# MMU8Ltqfp.net
KiCad netlist of a schematic drawn in EAGLE
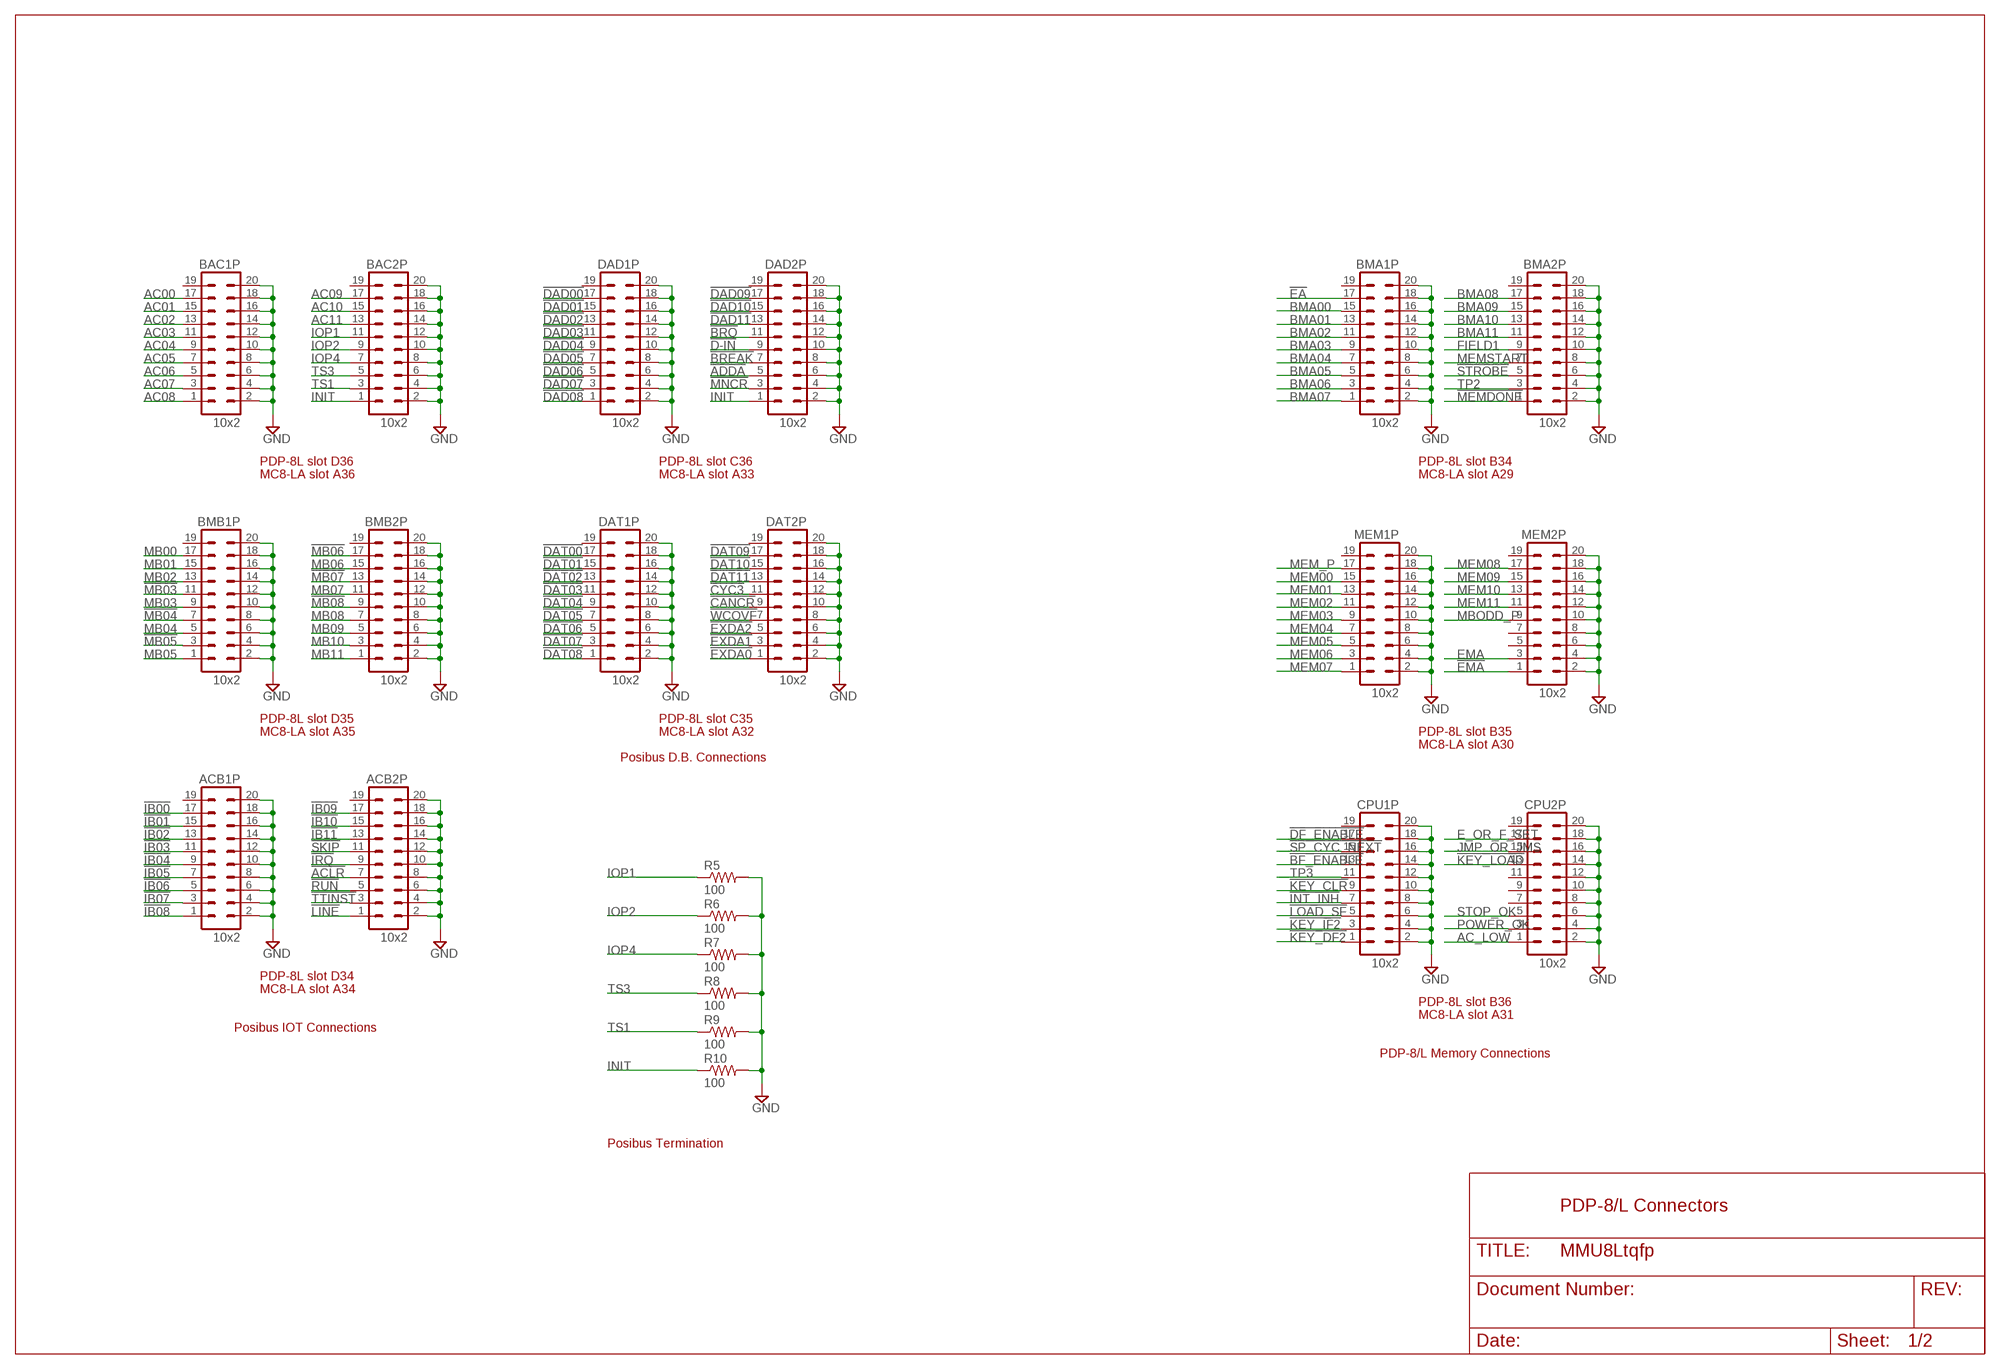
[diagram p0: schematic, sheet 1]
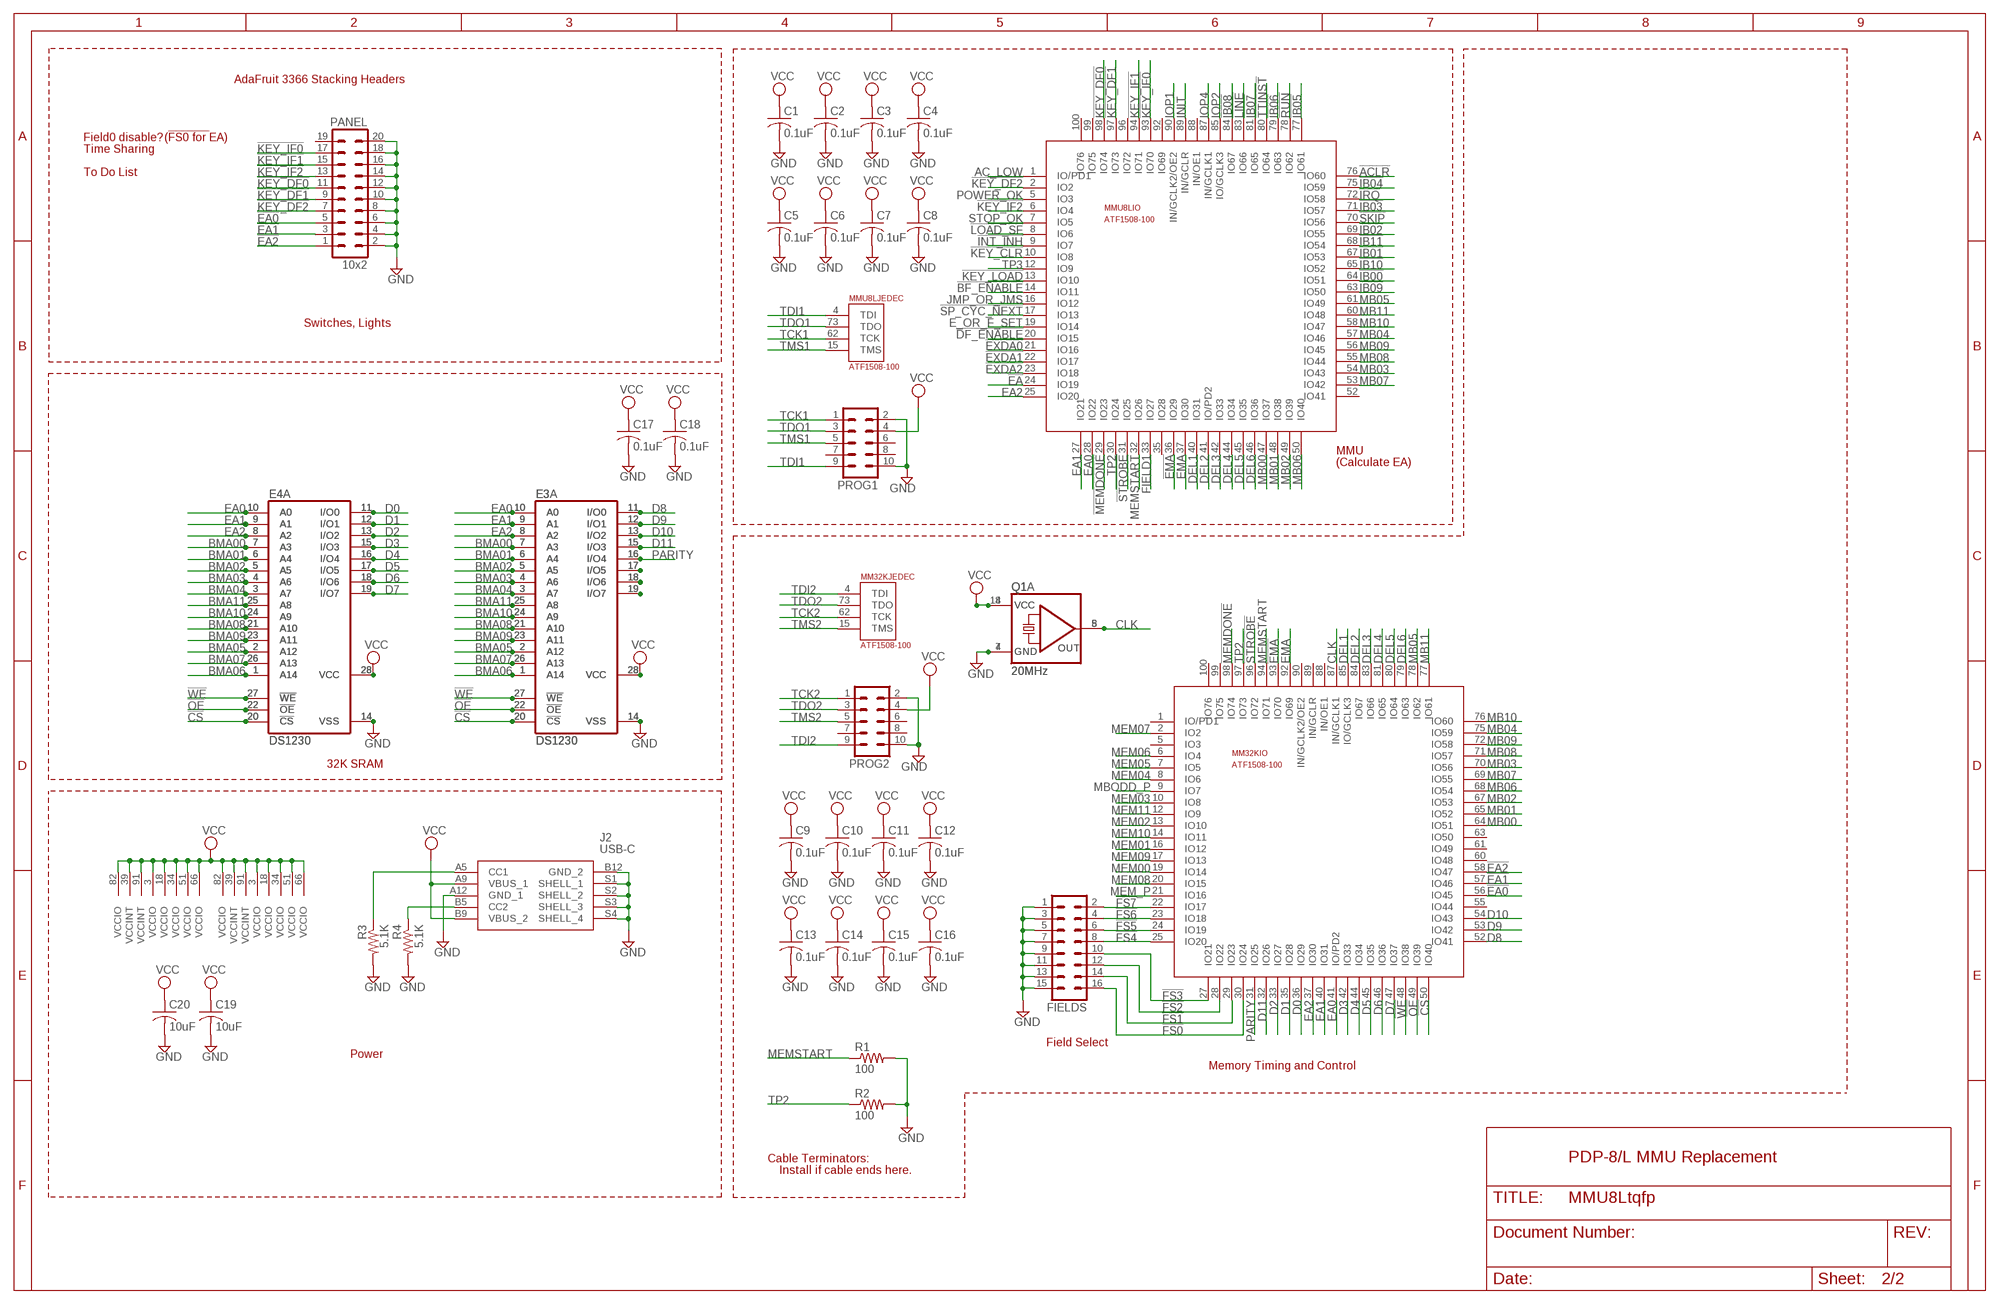
[diagram p1: schematic, sheet 2]

(export (version "E")
  (design (tool "Eeschema 10.0.6"))
  (components
    (comp (ref "ACB1P")
      (value "10x2")
      (footprint "eagle-import:MA10-2")
      (libsource (lib "eagle-import") (part "MA10-2"))
    )
    (comp (ref "ACB2P")
      (value "10x2")
      (footprint "eagle-import:MA10-2")
      (libsource (lib "eagle-import") (part "MA10-2"))
    )
    (comp (ref "BAC1P")
      (value "10x2")
      (footprint "eagle-import:MA10-2")
      (libsource (lib "eagle-import") (part "MA10-2"))
    )
    (comp (ref "BAC2P")
      (value "10x2")
      (footprint "eagle-import:MA10-2")
      (libsource (lib "eagle-import") (part "MA10-2"))
    )
    (comp (ref "BMA1P")
      (value "10x2")
      (footprint "eagle-import:MA10-2")
      (libsource (lib "eagle-import") (part "MA10-2"))
    )
    (comp (ref "BMA2P")
      (value "10x2")
      (footprint "eagle-import:MA10-2")
      (libsource (lib "eagle-import") (part "MA10-2"))
    )
    (comp (ref "BMB1P")
      (value "10x2")
      (footprint "eagle-import:MA10-2")
      (libsource (lib "eagle-import") (part "MA10-2"))
    )
    (comp (ref "BMB2P")
      (value "10x2")
      (footprint "eagle-import:MA10-2")
      (libsource (lib "eagle-import") (part "MA10-2"))
    )
    (comp (ref "CPU1P")
      (value "10x2")
      (footprint "eagle-import:MA10-2")
      (libsource (lib "eagle-import") (part "MA10-2"))
    )
    (comp (ref "CPU2P")
      (value "10x2")
      (footprint "eagle-import:MA10-2")
      (libsource (lib "eagle-import") (part "MA10-2"))
    )
    (comp (ref "DAD1P")
      (value "10x2")
      (footprint "eagle-import:MA10-2")
      (libsource (lib "eagle-import") (part "MA10-2"))
    )
    (comp (ref "DAD2P")
      (value "10x2")
      (footprint "eagle-import:MA10-2")
      (libsource (lib "eagle-import") (part "MA10-2"))
    )
    (comp (ref "DAT1P")
      (value "10x2")
      (footprint "eagle-import:MA10-2")
      (libsource (lib "eagle-import") (part "MA10-2"))
    )
    (comp (ref "DAT2P")
      (value "10x2")
      (footprint "eagle-import:MA10-2")
      (libsource (lib "eagle-import") (part "MA10-2"))
    )
    (comp (ref "MEM1P")
      (value "10x2")
      (footprint "eagle-import:MA10-2")
      (libsource (lib "eagle-import") (part "MA10-2"))
    )
    (comp (ref "MEM2P")
      (value "10x2")
      (footprint "eagle-import:MA10-2")
      (libsource (lib "eagle-import") (part "MA10-2"))
    )
    (comp (ref "R5")
      (value "100")
      (footprint "eagle-import:R1206")
      (libsource (lib "eagle-import") (part "R-US_R1206"))
    )
    (comp (ref "R6")
      (value "100")
      (footprint "eagle-import:R1206")
      (libsource (lib "eagle-import") (part "R-US_R1206"))
    )
    (comp (ref "R7")
      (value "100")
      (footprint "eagle-import:R1206")
      (libsource (lib "eagle-import") (part "R-US_R1206"))
    )
    (comp (ref "R8")
      (value "100")
      (footprint "eagle-import:R1206")
      (libsource (lib "eagle-import") (part "R-US_R1206"))
    )
    (comp (ref "R9")
      (value "100")
      (footprint "eagle-import:R1206")
      (libsource (lib "eagle-import") (part "R-US_R1206"))
    )
    (comp (ref "R10")
      (value "100")
      (footprint "eagle-import:R1206")
      (libsource (lib "eagle-import") (part "R-US_R1206"))
    )
    (comp (ref "C1")
      (value "0.1uF")
      (footprint "eagle-import:C0805")
      (libsource (lib "eagle-import") (part "C-USC0805"))
    )
    (comp (ref "C2")
      (value "0.1uF")
      (footprint "eagle-import:C0805")
      (libsource (lib "eagle-import") (part "C-USC0805"))
    )
    (comp (ref "C3")
      (value "0.1uF")
      (footprint "eagle-import:C0805")
      (libsource (lib "eagle-import") (part "C-USC0805"))
    )
    (comp (ref "C4")
      (value "0.1uF")
      (footprint "eagle-import:C0805")
      (libsource (lib "eagle-import") (part "C-USC0805"))
    )
    (comp (ref "C5")
      (value "0.1uF")
      (footprint "eagle-import:C0805")
      (libsource (lib "eagle-import") (part "C-USC0805"))
    )
    (comp (ref "C6")
      (value "0.1uF")
      (footprint "eagle-import:C0805")
      (libsource (lib "eagle-import") (part "C-USC0805"))
    )
    (comp (ref "C7")
      (value "0.1uF")
      (footprint "eagle-import:C0805")
      (libsource (lib "eagle-import") (part "C-USC0805"))
    )
    (comp (ref "C8")
      (value "0.1uF")
      (footprint "eagle-import:C0805")
      (libsource (lib "eagle-import") (part "C-USC0805"))
    )
    (comp (ref "C9")
      (value "0.1uF")
      (footprint "eagle-import:C0805")
      (libsource (lib "eagle-import") (part "C-USC0805"))
    )
    (comp (ref "C10")
      (value "0.1uF")
      (footprint "eagle-import:C0805")
      (libsource (lib "eagle-import") (part "C-USC0805"))
    )
    (comp (ref "C11")
      (value "0.1uF")
      (footprint "eagle-import:C0805")
      (libsource (lib "eagle-import") (part "C-USC0805"))
    )
    (comp (ref "C12")
      (value "0.1uF")
      (footprint "eagle-import:C0805")
      (libsource (lib "eagle-import") (part "C-USC0805"))
    )
    (comp (ref "C13")
      (value "0.1uF")
      (footprint "eagle-import:C0805")
      (libsource (lib "eagle-import") (part "C-USC0805"))
    )
    (comp (ref "C14")
      (value "0.1uF")
      (footprint "eagle-import:C0805")
      (libsource (lib "eagle-import") (part "C-USC0805"))
    )
    (comp (ref "C15")
      (value "0.1uF")
      (footprint "eagle-import:C0805")
      (libsource (lib "eagle-import") (part "C-USC0805"))
    )
    (comp (ref "C16")
      (value "0.1uF")
      (footprint "eagle-import:C0805")
      (libsource (lib "eagle-import") (part "C-USC0805"))
    )
    (comp (ref "C17")
      (value "0.1uF")
      (footprint "eagle-import:C0805")
      (libsource (lib "eagle-import") (part "C-USC0805"))
    )
    (comp (ref "C18")
      (value "0.1uF")
      (footprint "eagle-import:C0805")
      (libsource (lib "eagle-import") (part "C-USC0805"))
    )
    (comp (ref "C19")
      (value "10uF")
      (footprint "eagle-import:C0805")
      (libsource (lib "eagle-import") (part "C-USC0805"))
    )
    (comp (ref "C20")
      (value "10uF")
      (footprint "eagle-import:C0805")
      (libsource (lib "eagle-import") (part "C-USC0805"))
    )
    (comp (ref "E3")
      (value "DS1230")
      (footprint "eagle-import:DIL28-6")
      (libsource (lib "eagle-import") (part "62256P"))
    )
    (comp (ref "E3A")
      (value "DS1230")
      (footprint "eagle-import:DIL28-3")
      (libsource (lib "eagle-import") (part "62832P"))
    )
    (comp (ref "E4")
      (value "DS1230")
      (footprint "eagle-import:DIL28-6")
      (libsource (lib "eagle-import") (part "62256P"))
    )
    (comp (ref "E4A")
      (value "DS1230")
      (footprint "eagle-import:DIL28-3")
      (libsource (lib "eagle-import") (part "62832P"))
    )
    (comp (ref "FIELDS")
      (value "MA08-2")
      (footprint "eagle-import:MA08-2")
      (libsource (lib "eagle-import") (part "MA08-2"))
    )
    (comp (ref "J2")
      (value "USB-C")
      (footprint "eagle-import:USB497000A")
      (fields (field (name "MANUFACTURER_PART_NUMBER") "USB4970-00-A"))
      (libsource (lib "eagle-import") (part "USB4970-00-A"))
    )
    (comp (ref "MM32K")
      (value "ATF1508-100")
      (footprint "eagle-import:TQFP-100")
      (libsource (lib "eagle-import") (part "ATF150X100TQFP"))
    )
    (comp (ref "MMU8L")
      (value "ATF1508-100")
      (footprint "eagle-import:TQFP-100")
      (libsource (lib "eagle-import") (part "ATF150X100TQFP"))
    )
    (comp (ref "PANEL")
      (value "10x2")
      (footprint "eagle-import:MA10-2")
      (libsource (lib "eagle-import") (part "MA10-2"))
    )
    (comp (ref "PROG1")
      (value "ML10")
      (footprint "eagle-import:ML10")
      (libsource (lib "eagle-import") (part "ML10"))
    )
    (comp (ref "PROG2")
      (value "ML10")
      (footprint "eagle-import:ML10")
      (libsource (lib "eagle-import") (part "ML10"))
    )
    (comp (ref "Q1")
      (value "20MHz")
      (footprint "eagle-import:DIL14S")
      (libsource (lib "eagle-import") (part "QG5860"))
    )
    (comp (ref "Q1A")
      (value "20MHz")
      (footprint "eagle-import:DIL08S")
      (libsource (lib "eagle-import") (part "QG5460"))
    )
    (comp (ref "R1")
      (value "100")
      (footprint "eagle-import:R1206")
      (libsource (lib "eagle-import") (part "R-US_R1206"))
    )
    (comp (ref "R2")
      (value "100")
      (footprint "eagle-import:R1206")
      (libsource (lib "eagle-import") (part "R-US_R1206"))
    )
    (comp (ref "R3")
      (value "5.1K")
      (footprint "eagle-import:R0805")
      (libsource (lib "eagle-import") (part "R-US_R0805"))
    )
    (comp (ref "R4")
      (value "5.1K")
      (footprint "eagle-import:R0805")
      (libsource (lib "eagle-import") (part "R-US_R0805"))
    )
  )
  (nets
    (net (code "1") (name "AC00") (class "Default")
      (node (ref "BAC1P") (pin "17") (pinfunction "17_17") (pintype "passive"))
    )
    (net (code "2") (name "AC01") (class "Default")
      (node (ref "BAC1P") (pin "15") (pinfunction "15_15") (pintype "passive"))
    )
    (net (code "3") (name "AC02") (class "Default")
      (node (ref "BAC1P") (pin "13") (pinfunction "13_13") (pintype "passive"))
    )
    (net (code "4") (name "AC03") (class "Default")
      (node (ref "BAC1P") (pin "11") (pinfunction "11_11") (pintype "passive"))
    )
    (net (code "5") (name "AC04") (class "Default")
      (node (ref "BAC1P") (pin "9") (pinfunction "9_9") (pintype "passive"))
    )
    (net (code "6") (name "AC05") (class "Default")
      (node (ref "BAC1P") (pin "7") (pinfunction "7_7") (pintype "passive"))
    )
    (net (code "7") (name "AC06") (class "Default")
      (node (ref "BAC1P") (pin "5") (pinfunction "5_5") (pintype "passive"))
    )
    (net (code "8") (name "AC07") (class "Default")
      (node (ref "BAC1P") (pin "3") (pinfunction "3_3") (pintype "passive"))
    )
    (net (code "9") (name "AC08") (class "Default")
      (node (ref "BAC1P") (pin "1") (pinfunction "1_1") (pintype "passive"))
    )
    (net (code "10") (name "AC09") (class "Default")
      (node (ref "BAC2P") (pin "17") (pinfunction "17_17") (pintype "passive"))
    )
    (net (code "11") (name "AC10") (class "Default")
      (node (ref "BAC2P") (pin "15") (pinfunction "15_15") (pintype "passive"))
    )
    (net (code "12") (name "AC11") (class "Default")
      (node (ref "BAC2P") (pin "13") (pinfunction "13_13") (pintype "passive"))
    )
    (net (code "13") (name "AC_LOW") (class "Default")
      (node (ref "CPU2P") (pin "1") (pinfunction "1_1") (pintype "passive"))
      (node (ref "MMU8L") (pin "1") (pinfunction "IO/PD1_1") (pintype "bidirectional"))
    )
    (net (code "14") (name "BMA00") (class "Default")
      (node (ref "BMA1P") (pin "15") (pinfunction "15_15") (pintype "passive"))
      (node (ref "E3") (pin "7") (pinfunction "A3_7") (pintype "input"))
      (node (ref "E3A") (pin "7") (pinfunction "A3_7") (pintype "input"))
      (node (ref "E4") (pin "7") (pinfunction "A3_7") (pintype "input"))
      (node (ref "E4A") (pin "7") (pinfunction "A3_7") (pintype "input"))
    )
    (net (code "15") (name "BMA01") (class "Default")
      (node (ref "BMA1P") (pin "13") (pinfunction "13_13") (pintype "passive"))
      (node (ref "E3") (pin "6") (pinfunction "A4_6") (pintype "input"))
      (node (ref "E3A") (pin "6") (pinfunction "A4_6") (pintype "input"))
      (node (ref "E4") (pin "6") (pinfunction "A4_6") (pintype "input"))
      (node (ref "E4A") (pin "6") (pinfunction "A4_6") (pintype "input"))
    )
    (net (code "16") (name "BMA02") (class "Default")
      (node (ref "BMA1P") (pin "11") (pinfunction "11_11") (pintype "passive"))
      (node (ref "E3") (pin "5") (pinfunction "A5_5") (pintype "input"))
      (node (ref "E3A") (pin "5") (pinfunction "A5_5") (pintype "input"))
      (node (ref "E4") (pin "5") (pinfunction "A5_5") (pintype "input"))
      (node (ref "E4A") (pin "5") (pinfunction "A5_5") (pintype "input"))
    )
    (net (code "17") (name "BMA03") (class "Default")
      (node (ref "BMA1P") (pin "9") (pinfunction "9_9") (pintype "passive"))
      (node (ref "E3") (pin "4") (pinfunction "A6_4") (pintype "input"))
      (node (ref "E3A") (pin "4") (pinfunction "A6_4") (pintype "input"))
      (node (ref "E4") (pin "4") (pinfunction "A6_4") (pintype "input"))
      (node (ref "E4A") (pin "4") (pinfunction "A6_4") (pintype "input"))
    )
    (net (code "18") (name "BMA04") (class "Default")
      (node (ref "BMA1P") (pin "7") (pinfunction "7_7") (pintype "passive"))
      (node (ref "E3") (pin "3") (pinfunction "A7_3") (pintype "input"))
      (node (ref "E3A") (pin "3") (pinfunction "A7_3") (pintype "input"))
      (node (ref "E4") (pin "3") (pinfunction "A7_3") (pintype "input"))
      (node (ref "E4A") (pin "3") (pinfunction "A7_3") (pintype "input"))
    )
    (net (code "19") (name "BMA05") (class "Default")
      (node (ref "BMA1P") (pin "5") (pinfunction "5_5") (pintype "passive"))
      (node (ref "E3") (pin "2") (pinfunction "A12_2") (pintype "input"))
      (node (ref "E3A") (pin "2") (pinfunction "A12_2") (pintype "input"))
      (node (ref "E4") (pin "2") (pinfunction "A12_2") (pintype "input"))
      (node (ref "E4A") (pin "2") (pinfunction "A12_2") (pintype "input"))
    )
    (net (code "20") (name "BMA06") (class "Default")
      (node (ref "BMA1P") (pin "3") (pinfunction "3_3") (pintype "passive"))
      (node (ref "E3") (pin "1") (pinfunction "A14_1") (pintype "input"))
      (node (ref "E3A") (pin "1") (pinfunction "A14_1") (pintype "input"))
      (node (ref "E4") (pin "1") (pinfunction "A14_1") (pintype "input"))
      (node (ref "E4A") (pin "1") (pinfunction "A14_1") (pintype "input"))
    )
    (net (code "21") (name "BMA07") (class "Default")
      (node (ref "BMA1P") (pin "1") (pinfunction "1_1") (pintype "passive"))
      (node (ref "E3") (pin "26") (pinfunction "A13_26") (pintype "input"))
      (node (ref "E3A") (pin "26") (pinfunction "A13_26") (pintype "input"))
      (node (ref "E4") (pin "26") (pinfunction "A13_26") (pintype "input"))
      (node (ref "E4A") (pin "26") (pinfunction "A13_26") (pintype "input"))
    )
    (net (code "22") (name "BMA08") (class "Default")
      (node (ref "BMA2P") (pin "17") (pinfunction "17_17") (pintype "passive"))
      (node (ref "E3") (pin "21") (pinfunction "A10_21") (pintype "input"))
      (node (ref "E3A") (pin "21") (pinfunction "A10_21") (pintype "input"))
      (node (ref "E4") (pin "21") (pinfunction "A10_21") (pintype "input"))
      (node (ref "E4A") (pin "21") (pinfunction "A10_21") (pintype "input"))
    )
    (net (code "23") (name "BMA09") (class "Default")
      (node (ref "BMA2P") (pin "15") (pinfunction "15_15") (pintype "passive"))
      (node (ref "E3") (pin "23") (pinfunction "A11_23") (pintype "input"))
      (node (ref "E3A") (pin "23") (pinfunction "A11_23") (pintype "input"))
      (node (ref "E4") (pin "23") (pinfunction "A11_23") (pintype "input"))
      (node (ref "E4A") (pin "23") (pinfunction "A11_23") (pintype "input"))
    )
    (net (code "24") (name "BMA10") (class "Default")
      (node (ref "BMA2P") (pin "13") (pinfunction "13_13") (pintype "passive"))
      (node (ref "E3") (pin "24") (pinfunction "A9_24") (pintype "input"))
      (node (ref "E3A") (pin "24") (pinfunction "A9_24") (pintype "input"))
      (node (ref "E4") (pin "24") (pinfunction "A9_24") (pintype "input"))
      (node (ref "E4A") (pin "24") (pinfunction "A9_24") (pintype "input"))
    )
    (net (code "25") (name "BMA11") (class "Default")
      (node (ref "BMA2P") (pin "11") (pinfunction "11_11") (pintype "passive"))
      (node (ref "E3") (pin "25") (pinfunction "A8_25") (pintype "input"))
      (node (ref "E3A") (pin "25") (pinfunction "A8_25") (pintype "input"))
      (node (ref "E4") (pin "25") (pinfunction "A8_25") (pintype "input"))
      (node (ref "E4A") (pin "25") (pinfunction "A8_25") (pintype "input"))
    )
    (net (code "26") (name "CLK") (class "Default")
      (node (ref "MM32K") (pin "87") (pinfunction "IN/GCLK1_87") (pintype "input"))
      (node (ref "Q1") (pin "8") (pinfunction "OUT_8") (pintype "output"))
      (node (ref "Q1A") (pin "5") (pinfunction "OUT_5") (pintype "output"))
    )
    (net (code "27") (name "D0") (class "Default")
      (node (ref "E4") (pin "11") (pinfunction "I/O0_11") (pintype "bidirectional"))
      (node (ref "E4A") (pin "11") (pinfunction "I/O0_11") (pintype "bidirectional"))
      (node (ref "MM32K") (pin "36") (pinfunction "IO29_36") (pintype "bidirectional"))
    )
    (net (code "28") (name "D1") (class "Default")
      (node (ref "E4") (pin "12") (pinfunction "I/O1_12") (pintype "bidirectional"))
      (node (ref "E4A") (pin "12") (pinfunction "I/O1_12") (pintype "bidirectional"))
      (node (ref "MM32K") (pin "35") (pinfunction "IO28_35") (pintype "bidirectional"))
    )
    (net (code "29") (name "D2") (class "Default")
      (node (ref "E4") (pin "13") (pinfunction "I/O2_13") (pintype "bidirectional"))
      (node (ref "E4A") (pin "13") (pinfunction "I/O2_13") (pintype "bidirectional"))
      (node (ref "MM32K") (pin "33") (pinfunction "IO27_33") (pintype "bidirectional"))
    )
    (net (code "30") (name "D3") (class "Default")
      (node (ref "E4") (pin "15") (pinfunction "I/O3_15") (pintype "bidirectional"))
      (node (ref "E4A") (pin "15") (pinfunction "I/O3_15") (pintype "bidirectional"))
      (node (ref "MM32K") (pin "42") (pinfunction "IO33_42") (pintype "bidirectional"))
    )
    (net (code "31") (name "D4") (class "Default")
      (node (ref "E4") (pin "16") (pinfunction "I/O4_16") (pintype "bidirectional"))
      (node (ref "E4A") (pin "16") (pinfunction "I/O4_16") (pintype "bidirectional"))
      (node (ref "MM32K") (pin "44") (pinfunction "IO34_44") (pintype "bidirectional"))
    )
    (net (code "32") (name "D5") (class "Default")
      (node (ref "E4") (pin "17") (pinfunction "I/O5_17") (pintype "bidirectional"))
      (node (ref "E4A") (pin "17") (pinfunction "I/O5_17") (pintype "bidirectional"))
      (node (ref "MM32K") (pin "45") (pinfunction "IO35_45") (pintype "bidirectional"))
    )
    (net (code "33") (name "D6") (class "Default")
      (node (ref "E4") (pin "18") (pinfunction "I/O6_18") (pintype "bidirectional"))
      (node (ref "E4A") (pin "18") (pinfunction "I/O6_18") (pintype "bidirectional"))
      (node (ref "MM32K") (pin "46") (pinfunction "IO36_46") (pintype "bidirectional"))
    )
    (net (code "34") (name "D7") (class "Default")
      (node (ref "E4") (pin "19") (pinfunction "I/O7_19") (pintype "bidirectional"))
      (node (ref "E4A") (pin "19") (pinfunction "I/O7_19") (pintype "bidirectional"))
      (node (ref "MM32K") (pin "47") (pinfunction "IO37_47") (pintype "bidirectional"))
    )
    (net (code "35") (name "D8") (class "Default")
      (node (ref "E3") (pin "11") (pinfunction "I/O0_11") (pintype "bidirectional"))
      (node (ref "E3A") (pin "11") (pinfunction "I/O0_11") (pintype "bidirectional"))
      (node (ref "MM32K") (pin "52") (pinfunction "IO41_52") (pintype "bidirectional"))
    )
    (net (code "36") (name "D9") (class "Default")
      (node (ref "E3") (pin "12") (pinfunction "I/O1_12") (pintype "bidirectional"))
      (node (ref "E3A") (pin "12") (pinfunction "I/O1_12") (pintype "bidirectional"))
      (node (ref "MM32K") (pin "53") (pinfunction "IO42_53") (pintype "bidirectional"))
    )
    (net (code "37") (name "D10") (class "Default")
      (node (ref "E3") (pin "13") (pinfunction "I/O2_13") (pintype "bidirectional"))
      (node (ref "E3A") (pin "13") (pinfunction "I/O2_13") (pintype "bidirectional"))
      (node (ref "MM32K") (pin "54") (pinfunction "IO43_54") (pintype "bidirectional"))
    )
    (net (code "38") (name "D11") (class "Default")
      (node (ref "E3") (pin "15") (pinfunction "I/O3_15") (pintype "bidirectional"))
      (node (ref "E3A") (pin "15") (pinfunction "I/O3_15") (pintype "bidirectional"))
      (node (ref "MM32K") (pin "32") (pinfunction "IO26_32") (pintype "bidirectional"))
    )
    (net (code "39") (name "DEL1") (class "Default")
      (node (ref "MM32K") (pin "85") (pinfunction "IO/GCLK3_85") (pintype "bidirectional"))
      (node (ref "MMU8L") (pin "40") (pinfunction "IO31_40") (pintype "bidirectional"))
    )
    (net (code "40") (name "DEL2") (class "Default")
      (node (ref "MM32K") (pin "84") (pinfunction "IO67_84") (pintype "bidirectional"))
      (node (ref "MMU8L") (pin "41") (pinfunction "IO/PD2_41") (pintype "bidirectional"))
    )
    (net (code "41") (name "DEL3") (class "Default")
      (node (ref "MM32K") (pin "83") (pinfunction "IO66_83") (pintype "bidirectional"))
      (node (ref "MMU8L") (pin "42") (pinfunction "IO33_42") (pintype "bidirectional"))
    )
    (net (code "42") (name "DEL4") (class "Default")
      (node (ref "MM32K") (pin "81") (pinfunction "IO65_81") (pintype "bidirectional"))
      (node (ref "MMU8L") (pin "44") (pinfunction "IO34_44") (pintype "bidirectional"))
    )
    (net (code "43") (name "DEL5") (class "Default")
      (node (ref "MM32K") (pin "80") (pinfunction "IO64_80") (pintype "bidirectional"))
      (node (ref "MMU8L") (pin "45") (pinfunction "IO35_45") (pintype "bidirectional"))
    )
    (net (code "44") (name "DEL6") (class "Default")
      (node (ref "MM32K") (pin "79") (pinfunction "IO63_79") (pintype "bidirectional"))
      (node (ref "MMU8L") (pin "46") (pinfunction "IO36_46") (pintype "bidirectional"))
    )
    (net (code "45") (name "EA0") (class "Default")
      (node (ref "E3") (pin "10") (pinfunction "A0_10") (pintype "input"))
      (node (ref "E3A") (pin "10") (pinfunction "A0_10") (pintype "input"))
      (node (ref "E4") (pin "10") (pinfunction "A0_10") (pintype "input"))
      (node (ref "E4A") (pin "10") (pinfunction "A0_10") (pintype "input"))
      (node (ref "MM32K") (pin "41") (pinfunction "IO/PD2_41") (pintype "bidirectional"))
      (node (ref "MMU8L") (pin "28") (pinfunction "IO22_28") (pintype "bidirectional"))
    )
    (net (code "46") (name "EA1") (class "Default")
      (node (ref "E3") (pin "9") (pinfunction "A1_9") (pintype "input"))
      (node (ref "E3A") (pin "9") (pinfunction "A1_9") (pintype "input"))
      (node (ref "E4") (pin "9") (pinfunction "A1_9") (pintype "input"))
      (node (ref "E4A") (pin "9") (pinfunction "A1_9") (pintype "input"))
      (node (ref "MM32K") (pin "40") (pinfunction "IO31_40") (pintype "bidirectional"))
      (node (ref "MMU8L") (pin "27") (pinfunction "IO21_27") (pintype "bidirectional"))
    )
    (net (code "47") (name "EA2") (class "Default")
      (node (ref "E3") (pin "8") (pinfunction "A2_8") (pintype "input"))
      (node (ref "E3A") (pin "8") (pinfunction "A2_8") (pintype "input"))
      (node (ref "E4") (pin "8") (pinfunction "A2_8") (pintype "input"))
      (node (ref "E4A") (pin "8") (pinfunction "A2_8") (pintype "input"))
      (node (ref "MM32K") (pin "37") (pinfunction "IO30_37") (pintype "bidirectional"))
      (node (ref "MMU8L") (pin "25") (pinfunction "IO20_25") (pintype "bidirectional"))
    )
    (net (code "48") (name "EMA") (class "Default")
      (node (ref "MEM2P") (pin "3") (pinfunction "3_3") (pintype "passive"))
      (node (ref "MM32K") (pin "92") (pinfunction "IO69_92") (pintype "bidirectional"))
      (node (ref "MMU8L") (pin "37") (pinfunction "IO30_37") (pintype "bidirectional"))
    )
    (net (code "49") (name "E_OR_F_SET") (class "Default")
      (node (ref "CPU2P") (pin "17") (pinfunction "17_17") (pintype "passive"))
      (node (ref "MMU8L") (pin "19") (pinfunction "IO14_19") (pintype "bidirectional"))
    )
    (net (code "50") (name "FIELD1") (class "Default")
      (node (ref "BMA2P") (pin "9") (pinfunction "9_9") (pintype "passive"))
      (node (ref "MMU8L") (pin "33") (pinfunction "IO27_33") (pintype "bidirectional"))
    )
    (net (code "51") (name "GND") (class "Default")
      (node (ref "ACB1P") (pin "10") (pinfunction "10_10") (pintype "passive"))
      (node (ref "ACB1P") (pin "12") (pinfunction "12_12") (pintype "passive"))
      (node (ref "ACB1P") (pin "14") (pinfunction "14_14") (pintype "passive"))
      (node (ref "ACB1P") (pin "16") (pinfunction "16_16") (pintype "passive"))
      (node (ref "ACB1P") (pin "18") (pinfunction "18_18") (pintype "passive"))
      (node (ref "ACB1P") (pin "2") (pinfunction "2_2") (pintype "passive"))
      (node (ref "ACB1P") (pin "20") (pinfunction "20_20") (pintype "passive"))
      (node (ref "ACB1P") (pin "4") (pinfunction "4_4") (pintype "passive"))
      (node (ref "ACB1P") (pin "6") (pinfunction "6_6") (pintype "passive"))
      (node (ref "ACB1P") (pin "8") (pinfunction "8_8") (pintype "passive"))
      (node (ref "ACB2P") (pin "10") (pinfunction "10_10") (pintype "passive"))
      (node (ref "ACB2P") (pin "12") (pinfunction "12_12") (pintype "passive"))
      (node (ref "ACB2P") (pin "14") (pinfunction "14_14") (pintype "passive"))
      (node (ref "ACB2P") (pin "16") (pinfunction "16_16") (pintype "passive"))
      (node (ref "ACB2P") (pin "18") (pinfunction "18_18") (pintype "passive"))
      (node (ref "ACB2P") (pin "2") (pinfunction "2_2") (pintype "passive"))
      (node (ref "ACB2P") (pin "20") (pinfunction "20_20") (pintype "passive"))
      (node (ref "ACB2P") (pin "4") (pinfunction "4_4") (pintype "passive"))
      (node (ref "ACB2P") (pin "6") (pinfunction "6_6") (pintype "passive"))
      (node (ref "ACB2P") (pin "8") (pinfunction "8_8") (pintype "passive"))
      (node (ref "BAC1P") (pin "10") (pinfunction "10_10") (pintype "passive"))
      (node (ref "BAC1P") (pin "12") (pinfunction "12_12") (pintype "passive"))
      (node (ref "BAC1P") (pin "14") (pinfunction "14_14") (pintype "passive"))
      (node (ref "BAC1P") (pin "16") (pinfunction "16_16") (pintype "passive"))
      (node (ref "BAC1P") (pin "18") (pinfunction "18_18") (pintype "passive"))
      (node (ref "BAC1P") (pin "2") (pinfunction "2_2") (pintype "passive"))
      (node (ref "BAC1P") (pin "20") (pinfunction "20_20") (pintype "passive"))
      (node (ref "BAC1P") (pin "4") (pinfunction "4_4") (pintype "passive"))
      (node (ref "BAC1P") (pin "6") (pinfunction "6_6") (pintype "passive"))
      (node (ref "BAC1P") (pin "8") (pinfunction "8_8") (pintype "passive"))
      (node (ref "BAC2P") (pin "10") (pinfunction "10_10") (pintype "passive"))
      (node (ref "BAC2P") (pin "12") (pinfunction "12_12") (pintype "passive"))
      (node (ref "BAC2P") (pin "14") (pinfunction "14_14") (pintype "passive"))
      (node (ref "BAC2P") (pin "16") (pinfunction "16_16") (pintype "passive"))
      (node (ref "BAC2P") (pin "18") (pinfunction "18_18") (pintype "passive"))
      (node (ref "BAC2P") (pin "2") (pinfunction "2_2") (pintype "passive"))
      (node (ref "BAC2P") (pin "20") (pinfunction "20_20") (pintype "passive"))
      (node (ref "BAC2P") (pin "4") (pinfunction "4_4") (pintype "passive"))
      (node (ref "BAC2P") (pin "6") (pinfunction "6_6") (pintype "passive"))
      (node (ref "BAC2P") (pin "8") (pinfunction "8_8") (pintype "passive"))
      (node (ref "BMA1P") (pin "10") (pinfunction "10_10") (pintype "passive"))
      (node (ref "BMA1P") (pin "12") (pinfunction "12_12") (pintype "passive"))
      (node (ref "BMA1P") (pin "14") (pinfunction "14_14") (pintype "passive"))
      (node (ref "BMA1P") (pin "16") (pinfunction "16_16") (pintype "passive"))
      (node (ref "BMA1P") (pin "18") (pinfunction "18_18") (pintype "passive"))
      (node (ref "BMA1P") (pin "2") (pinfunction "2_2") (pintype "passive"))
      (node (ref "BMA1P") (pin "20") (pinfunction "20_20") (pintype "passive"))
      (node (ref "BMA1P") (pin "4") (pinfunction "4_4") (pintype "passive"))
      (node (ref "BMA1P") (pin "6") (pinfunction "6_6") (pintype "passive"))
      (node (ref "BMA1P") (pin "8") (pinfunction "8_8") (pintype "passive"))
      (node (ref "BMA2P") (pin "10") (pinfunction "10_10") (pintype "passive"))
      (node (ref "BMA2P") (pin "12") (pinfunction "12_12") (pintype "passive"))
      (node (ref "BMA2P") (pin "14") (pinfunction "14_14") (pintype "passive"))
      (node (ref "BMA2P") (pin "16") (pinfunction "16_16") (pintype "passive"))
      (node (ref "BMA2P") (pin "18") (pinfunction "18_18") (pintype "passive"))
      (node (ref "BMA2P") (pin "2") (pinfunction "2_2") (pintype "passive"))
      (node (ref "BMA2P") (pin "20") (pinfunction "20_20") (pintype "passive"))
      (node (ref "BMA2P") (pin "4") (pinfunction "4_4") (pintype "passive"))
      (node (ref "BMA2P") (pin "6") (pinfunction "6_6") (pintype "passive"))
      (node (ref "BMA2P") (pin "8") (pinfunction "8_8") (pintype "passive"))
      (node (ref "BMB1P") (pin "10") (pinfunction "10_10") (pintype "passive"))
      (node (ref "BMB1P") (pin "12") (pinfunction "12_12") (pintype "passive"))
      (node (ref "BMB1P") (pin "14") (pinfunction "14_14") (pintype "passive"))
      (node (ref "BMB1P") (pin "16") (pinfunction "16_16") (pintype "passive"))
      (node (ref "BMB1P") (pin "18") (pinfunction "18_18") (pintype "passive"))
      (node (ref "BMB1P") (pin "2") (pinfunction "2_2") (pintype "passive"))
      (node (ref "BMB1P") (pin "20") (pinfunction "20_20") (pintype "passive"))
      (node (ref "BMB1P") (pin "4") (pinfunction "4_4") (pintype "passive"))
      (node (ref "BMB1P") (pin "6") (pinfunction "6_6") (pintype "passive"))
      (node (ref "BMB1P") (pin "8") (pinfunction "8_8") (pintype "passive"))
      (node (ref "BMB2P") (pin "10") (pinfunction "10_10") (pintype "passive"))
      (node (ref "BMB2P") (pin "12") (pinfunction "12_12") (pintype "passive"))
      (node (ref "BMB2P") (pin "14") (pinfunction "14_14") (pintype "passive"))
      (node (ref "BMB2P") (pin "16") (pinfunction "16_16") (pintype "passive"))
      (node (ref "BMB2P") (pin "18") (pinfunction "18_18") (pintype "passive"))
      (node (ref "BMB2P") (pin "2") (pinfunction "2_2") (pintype "passive"))
      (node (ref "BMB2P") (pin "20") (pinfunction "20_20") (pintype "passive"))
      (node (ref "BMB2P") (pin "4") (pinfunction "4_4") (pintype "passive"))
      (node (ref "BMB2P") (pin "6") (pinfunction "6_6") (pintype "passive"))
      (node (ref "BMB2P") (pin "8") (pinfunction "8_8") (pintype "passive"))
      (node (ref "C1") (pin "2") (pinfunction "2_2") (pintype "passive"))
      (node (ref "C10") (pin "2") (pinfunction "2_2") (pintype "passive"))
      (node (ref "C11") (pin "2") (pinfunction "2_2") (pintype "passive"))
      (node (ref "C12") (pin "2") (pinfunction "2_2") (pintype "passive"))
      (node (ref "C13") (pin "2") (pinfunction "2_2") (pintype "passive"))
      (node (ref "C14") (pin "2") (pinfunction "2_2") (pintype "passive"))
      (node (ref "C15") (pin "2") (pinfunction "2_2") (pintype "passive"))
      (node (ref "C16") (pin "2") (pinfunction "2_2") (pintype "passive"))
      (node (ref "C17") (pin "2") (pinfunction "2_2") (pintype "passive"))
      (node (ref "C18") (pin "2") (pinfunction "2_2") (pintype "passive"))
      (node (ref "C19") (pin "2") (pinfunction "2_2") (pintype "passive"))
      (node (ref "C2") (pin "2") (pinfunction "2_2") (pintype "passive"))
      (node (ref "C20") (pin "2") (pinfunction "2_2") (pintype "passive"))
      (node (ref "C3") (pin "2") (pinfunction "2_2") (pintype "passive"))
      (node (ref "C4") (pin "2") (pinfunction "2_2") (pintype "passive"))
      (node (ref "C5") (pin "2") (pinfunction "2_2") (pintype "passive"))
      (node (ref "C6") (pin "2") (pinfunction "2_2") (pintype "passive"))
      (node (ref "C7") (pin "2") (pinfunction "2_2") (pintype "passive"))
      (node (ref "C8") (pin "2") (pinfunction "2_2") (pintype "passive"))
      (node (ref "C9") (pin "2") (pinfunction "2_2") (pintype "passive"))
      (node (ref "CPU1P") (pin "10") (pinfunction "10_10") (pintype "passive"))
      (node (ref "CPU1P") (pin "12") (pinfunction "12_12") (pintype "passive"))
      (node (ref "CPU1P") (pin "14") (pinfunction "14_14") (pintype "passive"))
      (node (ref "CPU1P") (pin "16") (pinfunction "16_16") (pintype "passive"))
      (node (ref "CPU1P") (pin "18") (pinfunction "18_18") (pintype "passive"))
      (node (ref "CPU1P") (pin "2") (pinfunction "2_2") (pintype "passive"))
      (node (ref "CPU1P") (pin "20") (pinfunction "20_20") (pintype "passive"))
      (node (ref "CPU1P") (pin "4") (pinfunction "4_4") (pintype "passive"))
      (node (ref "CPU1P") (pin "6") (pinfunction "6_6") (pintype "passive"))
      (node (ref "CPU1P") (pin "8") (pinfunction "8_8") (pintype "passive"))
      (node (ref "CPU2P") (pin "10") (pinfunction "10_10") (pintype "passive"))
      (node (ref "CPU2P") (pin "12") (pinfunction "12_12") (pintype "passive"))
      (node (ref "CPU2P") (pin "14") (pinfunction "14_14") (pintype "passive"))
      (node (ref "CPU2P") (pin "16") (pinfunction "16_16") (pintype "passive"))
      (node (ref "CPU2P") (pin "18") (pinfunction "18_18") (pintype "passive"))
      (node (ref "CPU2P") (pin "2") (pinfunction "2_2") (pintype "passive"))
      (node (ref "CPU2P") (pin "20") (pinfunction "20_20") (pintype "passive"))
      (node (ref "CPU2P") (pin "4") (pinfunction "4_4") (pintype "passive"))
      (node (ref "CPU2P") (pin "6") (pinfunction "6_6") (pintype "passive"))
      (node (ref "CPU2P") (pin "8") (pinfunction "8_8") (pintype "passive"))
      (node (ref "DAD1P") (pin "10") (pinfunction "10_10") (pintype "passive"))
      (node (ref "DAD1P") (pin "12") (pinfunction "12_12") (pintype "passive"))
      (node (ref "DAD1P") (pin "14") (pinfunction "14_14") (pintype "passive"))
      (node (ref "DAD1P") (pin "16") (pinfunction "16_16") (pintype "passive"))
      (node (ref "DAD1P") (pin "18") (pinfunction "18_18") (pintype "passive"))
      (node (ref "DAD1P") (pin "2") (pinfunction "2_2") (pintype "passive"))
      (node (ref "DAD1P") (pin "20") (pinfunction "20_20") (pintype "passive"))
      (node (ref "DAD1P") (pin "4") (pinfunction "4_4") (pintype "passive"))
      (node (ref "DAD1P") (pin "6") (pinfunction "6_6") (pintype "passive"))
      (node (ref "DAD1P") (pin "8") (pinfunction "8_8") (pintype "passive"))
      (node (ref "DAD2P") (pin "10") (pinfunction "10_10") (pintype "passive"))
      (node (ref "DAD2P") (pin "12") (pinfunction "12_12") (pintype "passive"))
      (node (ref "DAD2P") (pin "14") (pinfunction "14_14") (pintype "passive"))
      (node (ref "DAD2P") (pin "16") (pinfunction "16_16") (pintype "passive"))
      (node (ref "DAD2P") (pin "18") (pinfunction "18_18") (pintype "passive"))
      (node (ref "DAD2P") (pin "2") (pinfunction "2_2") (pintype "passive"))
      (node (ref "DAD2P") (pin "20") (pinfunction "20_20") (pintype "passive"))
      (node (ref "DAD2P") (pin "4") (pinfunction "4_4") (pintype "passive"))
      (node (ref "DAD2P") (pin "6") (pinfunction "6_6") (pintype "passive"))
      (node (ref "DAD2P") (pin "8") (pinfunction "8_8") (pintype "passive"))
      (node (ref "DAT1P") (pin "10") (pinfunction "10_10") (pintype "passive"))
      (node (ref "DAT1P") (pin "12") (pinfunction "12_12") (pintype "passive"))
      (node (ref "DAT1P") (pin "14") (pinfunction "14_14") (pintype "passive"))
      (node (ref "DAT1P") (pin "16") (pinfunction "16_16") (pintype "passive"))
      (node (ref "DAT1P") (pin "18") (pinfunction "18_18") (pintype "passive"))
      (node (ref "DAT1P") (pin "2") (pinfunction "2_2") (pintype "passive"))
      (node (ref "DAT1P") (pin "20") (pinfunction "20_20") (pintype "passive"))
      (node (ref "DAT1P") (pin "4") (pinfunction "4_4") (pintype "passive"))
      (node (ref "DAT1P") (pin "6") (pinfunction "6_6") (pintype "passive"))
      (node (ref "DAT1P") (pin "8") (pinfunction "8_8") (pintype "passive"))
      (node (ref "DAT2P") (pin "10") (pinfunction "10_10") (pintype "passive"))
      (node (ref "DAT2P") (pin "12") (pinfunction "12_12") (pintype "passive"))
      (node (ref "DAT2P") (pin "14") (pinfunction "14_14") (pintype "passive"))
      (node (ref "DAT2P") (pin "16") (pinfunction "16_16") (pintype "passive"))
      (node (ref "DAT2P") (pin "18") (pinfunction "18_18") (pintype "passive"))
      (node (ref "DAT2P") (pin "2") (pinfunction "2_2") (pintype "passive"))
      (node (ref "DAT2P") (pin "20") (pinfunction "20_20") (pintype "passive"))
      (node (ref "DAT2P") (pin "4") (pinfunction "4_4") (pintype "passive"))
      (node (ref "DAT2P") (pin "6") (pinfunction "6_6") (pintype "passive"))
      (node (ref "DAT2P") (pin "8") (pinfunction "8_8") (pintype "passive"))
      (node (ref "E3") (pin "14") (pinfunction "VSS_14") (pintype "power_in"))
      (node (ref "E3A") (pin "14") (pinfunction "VSS_14") (pintype "power_in"))
      (node (ref "E4") (pin "14") (pinfunction "VSS_14") (pintype "power_in"))
      (node (ref "E4A") (pin "14") (pinfunction "VSS_14") (pintype "power_in"))
      (node (ref "FIELDS") (pin "1") (pinfunction "1_1") (pintype "passive"))
      (node (ref "FIELDS") (pin "11") (pinfunction "11_11") (pintype "passive"))
      (node (ref "FIELDS") (pin "13") (pinfunction "13_13") (pintype "passive"))
      (node (ref "FIELDS") (pin "15") (pinfunction "15_15") (pintype "passive"))
      (node (ref "FIELDS") (pin "3") (pinfunction "3_3") (pintype "passive"))
      (node (ref "FIELDS") (pin "5") (pinfunction "5_5") (pintype "passive"))
      (node (ref "FIELDS") (pin "7") (pinfunction "7_7") (pintype "passive"))
      (node (ref "FIELDS") (pin "9") (pinfunction "9_9") (pintype "passive"))
      (node (ref "J2") (pin "A12") (pinfunction "GND_1_A12") (pintype "bidirectional"))
      (node (ref "J2") (pin "B12") (pinfunction "GND_2_B12") (pintype "bidirectional"))
      (node (ref "J2") (pin "S1") (pinfunction "SHELL_1_S1") (pintype "bidirectional"))
      (node (ref "J2") (pin "S2") (pinfunction "SHELL_2_S2") (pintype "bidirectional"))
      (node (ref "J2") (pin "S3") (pinfunction "SHELL_3_S3") (pintype "bidirectional"))
      (node (ref "J2") (pin "S4") (pinfunction "SHELL_4_S4") (pintype "bidirectional"))
      (node (ref "MEM1P") (pin "10") (pinfunction "10_10") (pintype "passive"))
      (node (ref "MEM1P") (pin "12") (pinfunction "12_12") (pintype "passive"))
      (node (ref "MEM1P") (pin "14") (pinfunction "14_14") (pintype "passive"))
      (node (ref "MEM1P") (pin "16") (pinfunction "16_16") (pintype "passive"))
      (node (ref "MEM1P") (pin "18") (pinfunction "18_18") (pintype "passive"))
      (node (ref "MEM1P") (pin "2") (pinfunction "2_2") (pintype "passive"))
      (node (ref "MEM1P") (pin "20") (pinfunction "20_20") (pintype "passive"))
      (node (ref "MEM1P") (pin "4") (pinfunction "4_4") (pintype "passive"))
      (node (ref "MEM1P") (pin "6") (pinfunction "6_6") (pintype "passive"))
      (node (ref "MEM1P") (pin "8") (pinfunction "8_8") (pintype "passive"))
      (node (ref "MEM2P") (pin "10") (pinfunction "10_10") (pintype "passive"))
      (node (ref "MEM2P") (pin "12") (pinfunction "12_12") (pintype "passive"))
      (node (ref "MEM2P") (pin "14") (pinfunction "14_14") (pintype "passive"))
      (node (ref "MEM2P") (pin "16") (pinfunction "16_16") (pintype "passive"))
      (node (ref "MEM2P") (pin "18") (pinfunction "18_18") (pintype "passive"))
      (node (ref "MEM2P") (pin "2") (pinfunction "2_2") (pintype "passive"))
      (node (ref "MEM2P") (pin "20") (pinfunction "20_20") (pintype "passive"))
      (node (ref "MEM2P") (pin "4") (pinfunction "4_4") (pintype "passive"))
      (node (ref "MEM2P") (pin "6") (pinfunction "6_6") (pintype "passive"))
      (node (ref "MEM2P") (pin "8") (pinfunction "8_8") (pintype "passive"))
      (node (ref "PANEL") (pin "10") (pinfunction "10_10") (pintype "passive"))
      (node (ref "PANEL") (pin "12") (pinfunction "12_12") (pintype "passive"))
      (node (ref "PANEL") (pin "14") (pinfunction "14_14") (pintype "passive"))
      (node (ref "PANEL") (pin "16") (pinfunction "16_16") (pintype "passive"))
      (node (ref "PANEL") (pin "18") (pinfunction "18_18") (pintype "passive"))
      (node (ref "PANEL") (pin "2") (pinfunction "2_2") (pintype "passive"))
      (node (ref "PANEL") (pin "20") (pinfunction "20_20") (pintype "passive"))
      (node (ref "PANEL") (pin "4") (pinfunction "4_4") (pintype "passive"))
      (node (ref "PANEL") (pin "6") (pinfunction "6_6") (pintype "passive"))
      (node (ref "PANEL") (pin "8") (pinfunction "8_8") (pintype "passive"))
      (node (ref "PROG1") (pin "10") (pinfunction "10_10") (pintype "passive"))
      (node (ref "PROG1") (pin "2") (pinfunction "2_2") (pintype "passive"))
      (node (ref "PROG2") (pin "10") (pinfunction "10_10") (pintype "passive"))
      (node (ref "PROG2") (pin "2") (pinfunction "2_2") (pintype "passive"))
      (node (ref "Q1") (pin "7") (pinfunction "GND_7") (pintype "power_in"))
      (node (ref "Q1A") (pin "4") (pinfunction "GND_4") (pintype "power_in"))
      (node (ref "R1") (pin "2") (pinfunction "2_2") (pintype "passive"))
      (node (ref "R10") (pin "2") (pinfunction "2_2") (pintype "passive"))
      (node (ref "R2") (pin "2") (pinfunction "2_2") (pintype "passive"))
      (node (ref "R3") (pin "2") (pinfunction "2_2") (pintype "passive"))
      (node (ref "R4") (pin "2") (pinfunction "2_2") (pintype "passive"))
      (node (ref "R5") (pin "2") (pinfunction "2_2") (pintype "passive"))
      (node (ref "R6") (pin "2") (pinfunction "2_2") (pintype "passive"))
      (node (ref "R7") (pin "2") (pinfunction "2_2") (pintype "passive"))
      (node (ref "R8") (pin "2") (pinfunction "2_2") (pintype "passive"))
      (node (ref "R9") (pin "2") (pinfunction "2_2") (pintype "passive"))
    )
    (net (code "52") (name "INIT") (class "Default")
      (node (ref "BAC2P") (pin "1") (pinfunction "1_1") (pintype "passive"))
      (node (ref "DAD2P") (pin "1") (pinfunction "1_1") (pintype "passive"))
      (node (ref "MMU8L") (pin "89") (pinfunction "IN/GCLR_89") (pintype "input"))
      (node (ref "R10") (pin "1") (pinfunction "1_1") (pintype "passive"))
    )
    (net (code "53") (name "IOP1") (class "Default")
      (node (ref "BAC2P") (pin "11") (pinfunction "11_11") (pintype "passive"))
      (node (ref "MMU8L") (pin "90") (pinfunction "IN/GCLK2/OE2_90") (pintype "input"))
      (node (ref "R5") (pin "1") (pinfunction "1_1") (pintype "passive"))
    )
    (net (code "54") (name "IOP2") (class "Default")
      (node (ref "BAC2P") (pin "9") (pinfunction "9_9") (pintype "passive"))
      (node (ref "MMU8L") (pin "85") (pinfunction "IO/GCLK3_85") (pintype "bidirectional"))
      (node (ref "R6") (pin "1") (pinfunction "1_1") (pintype "passive"))
    )
    (net (code "55") (name "IOP4") (class "Default")
      (node (ref "BAC2P") (pin "7") (pinfunction "7_7") (pintype "passive"))
      (node (ref "MMU8L") (pin "87") (pinfunction "IN/GCLK1_87") (pintype "input"))
      (node (ref "R7") (pin "1") (pinfunction "1_1") (pintype "passive"))
    )
    (net (code "56") (name "JMP_OR_JMS") (class "Default")
      (node (ref "CPU2P") (pin "15") (pinfunction "15_15") (pintype "passive"))
      (node (ref "MMU8L") (pin "16") (pinfunction "IO12_16") (pintype "bidirectional"))
    )
    (net (code "57") (name "MB00") (class "Default")
      (node (ref "BMB1P") (pin "17") (pinfunction "17_17") (pintype "passive"))
      (node (ref "MM32K") (pin "64") (pinfunction "IO51_64") (pintype "bidirectional"))
      (node (ref "MMU8L") (pin "47") (pinfunction "IO37_47") (pintype "bidirectional"))
    )
    (net (code "58") (name "MB01") (class "Default")
      (node (ref "BMB1P") (pin "15") (pinfunction "15_15") (pintype "passive"))
      (node (ref "MM32K") (pin "65") (pinfunction "IO52_65") (pintype "bidirectional"))
      (node (ref "MMU8L") (pin "48") (pinfunction "IO38_48") (pintype "bidirectional"))
    )
    (net (code "59") (name "MB02") (class "Default")
      (node (ref "BMB1P") (pin "13") (pinfunction "13_13") (pintype "passive"))
      (node (ref "MM32K") (pin "67") (pinfunction "IO53_67") (pintype "bidirectional"))
      (node (ref "MMU8L") (pin "49") (pinfunction "IO39_49") (pintype "bidirectional"))
    )
    (net (code "60") (name "MB03") (class "Default")
      (node (ref "BMB1P") (pin "9") (pinfunction "9_9") (pintype "passive"))
      (node (ref "MM32K") (pin "70") (pinfunction "IO56_70") (pintype "bidirectional"))
      (node (ref "MMU8L") (pin "54") (pinfunction "IO43_54") (pintype "bidirectional"))
    )
    (net (code "61") (name "MB04") (class "Default")
      (node (ref "BMB1P") (pin "5") (pinfunction "5_5") (pintype "passive"))
      (node (ref "MM32K") (pin "75") (pinfunction "IO59_75") (pintype "bidirectional"))
      (node (ref "MMU8L") (pin "57") (pinfunction "IO46_57") (pintype "bidirectional"))
    )
    (net (code "62") (name "MB05") (class "Default")
      (node (ref "BMB1P") (pin "1") (pinfunction "1_1") (pintype "passive"))
      (node (ref "MM32K") (pin "78") (pinfunction "IO62_78") (pintype "bidirectional"))
      (node (ref "MMU8L") (pin "61") (pinfunction "IO49_61") (pintype "bidirectional"))
    )
    (net (code "63") (name "MB06") (class "Default")
      (node (ref "BMB2P") (pin "15") (pinfunction "15_15") (pintype "passive"))
      (node (ref "MM32K") (pin "68") (pinfunction "IO54_68") (pintype "bidirectional"))
      (node (ref "MMU8L") (pin "50") (pinfunction "IO40_50") (pintype "bidirectional"))
    )
    (net (code "64") (name "MB07") (class "Default")
      (node (ref "BMB2P") (pin "11") (pinfunction "11_11") (pintype "passive"))
      (node (ref "MM32K") (pin "69") (pinfunction "IO55_69") (pintype "bidirectional"))
      (node (ref "MMU8L") (pin "53") (pinfunction "IO42_53") (pintype "bidirectional"))
    )
    (net (code "65") (name "MB08") (class "Default")
      (node (ref "BMB2P") (pin "7") (pinfunction "7_7") (pintype "passive"))
      (node (ref "MM32K") (pin "71") (pinfunction "IO57_71") (pintype "bidirectional"))
      (node (ref "MMU8L") (pin "55") (pinfunction "IO44_55") (pintype "bidirectional"))
    )
    (net (code "66") (name "MB09") (class "Default")
      (node (ref "BMB2P") (pin "5") (pinfunction "5_5") (pintype "passive"))
      (node (ref "MM32K") (pin "72") (pinfunction "IO58_72") (pintype "bidirectional"))
      (node (ref "MMU8L") (pin "56") (pinfunction "IO45_56") (pintype "bidirectional"))
    )
    (net (code "67") (name "MB10") (class "Default")
      (node (ref "BMB2P") (pin "3") (pinfunction "3_3") (pintype "passive"))
      (node (ref "MM32K") (pin "76") (pinfunction "IO60_76") (pintype "bidirectional"))
      (node (ref "MMU8L") (pin "58") (pinfunction "IO47_58") (pintype "bidirectional"))
    )
    (net (code "68") (name "MB11") (class "Default")
      (node (ref "BMB2P") (pin "1") (pinfunction "1_1") (pintype "passive"))
      (node (ref "MM32K") (pin "77") (pinfunction "IO61_77") (pintype "bidirectional"))
      (node (ref "MMU8L") (pin "60") (pinfunction "IO48_60") (pintype "bidirectional"))
    )
    (net (code "69") (name "MBODD_P") (class "Default")
      (node (ref "MEM2P") (pin "9") (pinfunction "9_9") (pintype "passive"))
      (node (ref "MM32K") (pin "9") (pinfunction "IO7_9") (pintype "bidirectional"))
    )
    (net (code "70") (name "MEM00") (class "Default")
      (node (ref "MEM1P") (pin "15") (pinfunction "15_15") (pintype "passive"))
      (node (ref "MM32K") (pin "19") (pinfunction "IO14_19") (pintype "bidirectional"))
    )
    (net (code "71") (name "MEM01") (class "Default")
      (node (ref "MEM1P") (pin "13") (pinfunction "13_13") (pintype "passive"))
      (node (ref "MM32K") (pin "16") (pinfunction "IO12_16") (pintype "bidirectional"))
    )
    (net (code "72") (name "MEM02") (class "Default")
      (node (ref "MEM1P") (pin "11") (pinfunction "11_11") (pintype "passive"))
      (node (ref "MM32K") (pin "13") (pinfunction "IO10_13") (pintype "bidirectional"))
    )
    (net (code "73") (name "MEM03") (class "Default")
      (node (ref "MEM1P") (pin "9") (pinfunction "9_9") (pintype "passive"))
      (node (ref "MM32K") (pin "10") (pinfunction "IO8_10") (pintype "bidirectional"))
    )
    (net (code "74") (name "MEM04") (class "Default")
      (node (ref "MEM1P") (pin "7") (pinfunction "7_7") (pintype "passive"))
      (node (ref "MM32K") (pin "8") (pinfunction "IO6_8") (pintype "bidirectional"))
    )
    (net (code "75") (name "MEM05") (class "Default")
      (node (ref "MEM1P") (pin "5") (pinfunction "5_5") (pintype "passive"))
      (node (ref "MM32K") (pin "7") (pinfunction "IO5_7") (pintype "bidirectional"))
    )
    (net (code "76") (name "MEM06") (class "Default")
      (node (ref "MEM1P") (pin "3") (pinfunction "3_3") (pintype "passive"))
      (node (ref "MM32K") (pin "6") (pinfunction "IO4_6") (pintype "bidirectional"))
    )
    (net (code "77") (name "MEM07") (class "Default")
      (node (ref "MEM1P") (pin "1") (pinfunction "1_1") (pintype "passive"))
      (node (ref "MM32K") (pin "2") (pinfunction "IO2_2") (pintype "bidirectional"))
    )
    (net (code "78") (name "MEM08") (class "Default")
      (node (ref "MEM2P") (pin "17") (pinfunction "17_17") (pintype "passive"))
      (node (ref "MM32K") (pin "20") (pinfunction "IO15_20") (pintype "bidirectional"))
    )
    (net (code "79") (name "MEM09") (class "Default")
      (node (ref "MEM2P") (pin "15") (pinfunction "15_15") (pintype "passive"))
      (node (ref "MM32K") (pin "17") (pinfunction "IO13_17") (pintype "bidirectional"))
    )
    (net (code "80") (name "MEM10") (class "Default")
      (node (ref "MEM2P") (pin "13") (pinfunction "13_13") (pintype "passive"))
      (node (ref "MM32K") (pin "14") (pinfunction "IO11_14") (pintype "bidirectional"))
    )
    (net (code "81") (name "MEM11") (class "Default")
      (node (ref "MEM2P") (pin "11") (pinfunction "11_11") (pintype "passive"))
      (node (ref "MM32K") (pin "12") (pinfunction "IO9_12") (pintype "bidirectional"))
    )
    (net (code "82") (name "MEMSTART") (class "Default")
      (node (ref "BMA2P") (pin "7") (pinfunction "7_7") (pintype "passive"))
      (node (ref "MM32K") (pin "94") (pinfunction "IO71_94") (pintype "bidirectional"))
      (node (ref "MMU8L") (pin "32") (pinfunction "IO26_32") (pintype "bidirectional"))
      (node (ref "R1") (pin "1") (pinfunction "1_1") (pintype "passive"))
    )
    (net (code "83") (name "MEM_P") (class "Default")
      (node (ref "MEM1P") (pin "17") (pinfunction "17_17") (pintype "passive"))
      (node (ref "MM32K") (pin "21") (pinfunction "IO16_21") (pintype "bidirectional"))
    )
    (net (code "84") (name "Net-(E3-I{slash}O5)") (class "Default")
      (node (ref "E3") (pin "17") (pinfunction "I/O5_17") (pintype "bidirectional"))
      (node (ref "E3A") (pin "17") (pinfunction "I/O5_17") (pintype "bidirectional"))
    )
    (net (code "85") (name "Net-(E3-I{slash}O6)") (class "Default")
      (node (ref "E3") (pin "18") (pinfunction "I/O6_18") (pintype "bidirectional"))
      (node (ref "E3A") (pin "18") (pinfunction "I/O6_18") (pintype "bidirectional"))
    )
    (net (code "86") (name "Net-(E3-I{slash}O7)") (class "Default")
      (node (ref "E3") (pin "19") (pinfunction "I/O7_19") (pintype "bidirectional"))
      (node (ref "E3A") (pin "19") (pinfunction "I/O7_19") (pintype "bidirectional"))
    )
    (net (code "87") (name "Net-(J2-CC1)") (class "Default")
      (node (ref "J2") (pin "A5") (pinfunction "CC1_A5") (pintype "bidirectional"))
      (node (ref "R3") (pin "1") (pinfunction "1_1") (pintype "passive"))
    )
    (net (code "88") (name "Net-(J2-CC2)") (class "Default")
      (node (ref "J2") (pin "B5") (pinfunction "CC2_B5") (pintype "bidirectional"))
      (node (ref "R4") (pin "1") (pinfunction "1_1") (pintype "passive"))
    )
    (net (code "89") (name "PARITY") (class "Default")
      (node (ref "E3") (pin "16") (pinfunction "I/O4_16") (pintype "bidirectional"))
      (node (ref "E3A") (pin "16") (pinfunction "I/O4_16") (pintype "bidirectional"))
      (node (ref "MM32K") (pin "31") (pinfunction "IO25_31") (pintype "bidirectional"))
    )
    (net (code "90") (name "POWER_OK") (class "Default")
      (node (ref "CPU2P") (pin "3") (pinfunction "3_3") (pintype "passive"))
      (node (ref "MMU8L") (pin "5") (pinfunction "IO3_5") (pintype "bidirectional"))
    )
    (net (code "91") (name "STOP_OK") (class "Default")
      (node (ref "CPU2P") (pin "5") (pinfunction "5_5") (pintype "passive"))
      (node (ref "MMU8L") (pin "7") (pinfunction "IO5_7") (pintype "bidirectional"))
    )
    (net (code "92") (name "TCK1") (class "Default")
      (node (ref "MMU8L") (pin "62") (pinfunction "TCK_62") (pintype "bidirectional"))
      (node (ref "PROG1") (pin "1") (pinfunction "1_1") (pintype "passive"))
    )
    (net (code "93") (name "TCK2") (class "Default")
      (node (ref "MM32K") (pin "62") (pinfunction "TCK_62") (pintype "bidirectional"))
      (node (ref "PROG2") (pin "1") (pinfunction "1_1") (pintype "passive"))
    )
    (net (code "94") (name "TDI1") (class "Default")
      (node (ref "MMU8L") (pin "4") (pinfunction "TDI_4") (pintype "bidirectional"))
      (node (ref "PROG1") (pin "9") (pinfunction "9_9") (pintype "passive"))
    )
    (net (code "95") (name "TDI2") (class "Default")
      (node (ref "MM32K") (pin "4") (pinfunction "TDI_4") (pintype "bidirectional"))
      (node (ref "PROG2") (pin "9") (pinfunction "9_9") (pintype "passive"))
    )
    (net (code "96") (name "TDO1") (class "Default")
      (node (ref "MMU8L") (pin "73") (pinfunction "TDO_73") (pintype "bidirectional"))
      (node (ref "PROG1") (pin "3") (pinfunction "3_3") (pintype "passive"))
    )
    (net (code "97") (name "TDO2") (class "Default")
      (node (ref "MM32K") (pin "73") (pinfunction "TDO_73") (pintype "bidirectional"))
      (node (ref "PROG2") (pin "3") (pinfunction "3_3") (pintype "passive"))
    )
    (net (code "98") (name "TMS1") (class "Default")
      (node (ref "MMU8L") (pin "15") (pinfunction "TMS_15") (pintype "bidirectional"))
      (node (ref "PROG1") (pin "5") (pinfunction "5_5") (pintype "passive"))
    )
    (net (code "99") (name "TMS2") (class "Default")
      (node (ref "MM32K") (pin "15") (pinfunction "TMS_15") (pintype "bidirectional"))
      (node (ref "PROG2") (pin "5") (pinfunction "5_5") (pintype "passive"))
    )
    (net (code "100") (name "TP2") (class "Default")
      (node (ref "BMA2P") (pin "3") (pinfunction "3_3") (pintype "passive"))
      (node (ref "MM32K") (pin "97") (pinfunction "IO73_97") (pintype "bidirectional"))
      (node (ref "MMU8L") (pin "30") (pinfunction "IO24_30") (pintype "bidirectional"))
      (node (ref "R2") (pin "1") (pinfunction "1_1") (pintype "passive"))
    )
    (net (code "101") (name "TP3") (class "Default")
      (node (ref "CPU1P") (pin "11") (pinfunction "11_11") (pintype "passive"))
      (node (ref "MMU8L") (pin "12") (pinfunction "IO9_12") (pintype "bidirectional"))
    )
    (net (code "102") (name "TS1") (class "Default")
      (node (ref "BAC2P") (pin "3") (pinfunction "3_3") (pintype "passive"))
      (node (ref "R9") (pin "1") (pinfunction "1_1") (pintype "passive"))
    )
    (net (code "103") (name "TS3") (class "Default")
      (node (ref "BAC2P") (pin "5") (pinfunction "5_5") (pintype "passive"))
      (node (ref "R8") (pin "1") (pinfunction "1_1") (pintype "passive"))
    )
    (net (code "104") (name "VCC") (class "Default")
      (node (ref "C1") (pin "1") (pinfunction "1_1") (pintype "passive"))
      (node (ref "C10") (pin "1") (pinfunction "1_1") (pintype "passive"))
      (node (ref "C11") (pin "1") (pinfunction "1_1") (pintype "passive"))
      (node (ref "C12") (pin "1") (pinfunction "1_1") (pintype "passive"))
      (node (ref "C13") (pin "1") (pinfunction "1_1") (pintype "passive"))
      (node (ref "C14") (pin "1") (pinfunction "1_1") (pintype "passive"))
      (node (ref "C15") (pin "1") (pinfunction "1_1") (pintype "passive"))
      (node (ref "C16") (pin "1") (pinfunction "1_1") (pintype "passive"))
      (node (ref "C17") (pin "1") (pinfunction "1_1") (pintype "passive"))
      (node (ref "C18") (pin "1") (pinfunction "1_1") (pintype "passive"))
      (node (ref "C19") (pin "1") (pinfunction "1_1") (pintype "passive"))
      (node (ref "C2") (pin "1") (pinfunction "1_1") (pintype "passive"))
      (node (ref "C20") (pin "1") (pinfunction "1_1") (pintype "passive"))
      (node (ref "C3") (pin "1") (pinfunction "1_1") (pintype "passive"))
      (node (ref "C4") (pin "1") (pinfunction "1_1") (pintype "passive"))
      (node (ref "C5") (pin "1") (pinfunction "1_1") (pintype "passive"))
      (node (ref "C6") (pin "1") (pinfunction "1_1") (pintype "passive"))
      (node (ref "C7") (pin "1") (pinfunction "1_1") (pintype "passive"))
      (node (ref "C8") (pin "1") (pinfunction "1_1") (pintype "passive"))
      (node (ref "C9") (pin "1") (pinfunction "1_1") (pintype "passive"))
      (node (ref "E3") (pin "28") (pinfunction "VCC_28") (pintype "power_in"))
      (node (ref "E3A") (pin "28") (pinfunction "VCC_28") (pintype "power_in"))
      (node (ref "E4") (pin "28") (pinfunction "VCC_28") (pintype "power_in"))
      (node (ref "E4A") (pin "28") (pinfunction "VCC_28") (pintype "power_in"))
      (node (ref "J2") (pin "A9") (pinfunction "VBUS_1_A9") (pintype "bidirectional"))
      (node (ref "J2") (pin "B9") (pinfunction "VBUS_2_B9") (pintype "bidirectional"))
      (node (ref "MM32K") (pin "18") (pinfunction "VCCIO_18") (pintype "power_in"))
      (node (ref "MM32K") (pin "3") (pinfunction "VCCIO_3") (pintype "power_in"))
      (node (ref "MM32K") (pin "34") (pinfunction "VCCIO_34") (pintype "power_in"))
      (node (ref "MM32K") (pin "39") (pinfunction "VCCINT_39") (pintype "power_in"))
      (node (ref "MM32K") (pin "51") (pinfunction "VCCIO_51") (pintype "power_in"))
      (node (ref "MM32K") (pin "66") (pinfunction "VCCIO_66") (pintype "power_in"))
      (node (ref "MM32K") (pin "82") (pinfunction "VCCIO_82") (pintype "power_in"))
      (node (ref "MM32K") (pin "91") (pinfunction "VCCINT_91") (pintype "power_in"))
      (node (ref "MMU8L") (pin "18") (pinfunction "VCCIO_18") (pintype "power_in"))
      (node (ref "MMU8L") (pin "3") (pinfunction "VCCIO_3") (pintype "power_in"))
      (node (ref "MMU8L") (pin "34") (pinfunction "VCCIO_34") (pintype "power_in"))
      (node (ref "MMU8L") (pin "39") (pinfunction "VCCINT_39") (pintype "power_in"))
      (node (ref "MMU8L") (pin "51") (pinfunction "VCCIO_51") (pintype "power_in"))
      (node (ref "MMU8L") (pin "66") (pinfunction "VCCIO_66") (pintype "power_in"))
      (node (ref "MMU8L") (pin "82") (pinfunction "VCCIO_82") (pintype "power_in"))
      (node (ref "MMU8L") (pin "91") (pinfunction "VCCINT_91") (pintype "power_in"))
      (node (ref "PROG1") (pin "4") (pinfunction "4_4") (pintype "passive"))
      (node (ref "PROG2") (pin "4") (pinfunction "4_4") (pintype "passive"))
      (node (ref "Q1") (pin "14") (pinfunction "VCC_14") (pintype "power_in"))
      (node (ref "Q1A") (pin "8") (pinfunction "VCC_8") (pintype "power_in"))
    )
    (net (code "105") (name "unconnected-(ACB1P-Pad19)") (class "Default")
      (node (ref "ACB1P") (pin "19") (pinfunction "19_19") (pintype "passive"))
    )
    (net (code "106") (name "unconnected-(ACB2P-Pad19)") (class "Default")
      (node (ref "ACB2P") (pin "19") (pinfunction "19_19") (pintype "passive"))
    )
    (net (code "107") (name "unconnected-(BAC1P-Pad19)") (class "Default")
      (node (ref "BAC1P") (pin "19") (pinfunction "19_19") (pintype "passive"))
    )
    (net (code "108") (name "unconnected-(BAC2P-Pad19)") (class "Default")
      (node (ref "BAC2P") (pin "19") (pinfunction "19_19") (pintype "passive"))
    )
    (net (code "109") (name "unconnected-(BMA1P-Pad19)") (class "Default")
      (node (ref "BMA1P") (pin "19") (pinfunction "19_19") (pintype "passive"))
    )
    (net (code "110") (name "unconnected-(BMA2P-Pad19)") (class "Default")
      (node (ref "BMA2P") (pin "19") (pinfunction "19_19") (pintype "passive"))
    )
    (net (code "111") (name "unconnected-(BMB1P-Pad19)") (class "Default")
      (node (ref "BMB1P") (pin "19") (pinfunction "19_19") (pintype "passive"))
    )
    (net (code "112") (name "unconnected-(BMB2P-Pad19)") (class "Default")
      (node (ref "BMB2P") (pin "19") (pinfunction "19_19") (pintype "passive"))
    )
    (net (code "113") (name "unconnected-(CPU1P-Pad19)") (class "Default")
      (node (ref "CPU1P") (pin "19") (pinfunction "19_19") (pintype "passive"))
    )
    (net (code "114") (name "unconnected-(CPU2P-Pad7)") (class "Default")
      (node (ref "CPU2P") (pin "7") (pinfunction "7_7") (pintype "passive"))
    )
    (net (code "115") (name "unconnected-(CPU2P-Pad9)") (class "Default")
      (node (ref "CPU2P") (pin "9") (pinfunction "9_9") (pintype "passive"))
    )
    (net (code "116") (name "unconnected-(CPU2P-Pad11)") (class "Default")
      (node (ref "CPU2P") (pin "11") (pinfunction "11_11") (pintype "passive"))
    )
    (net (code "117") (name "unconnected-(CPU2P-Pad19)") (class "Default")
      (node (ref "CPU2P") (pin "19") (pinfunction "19_19") (pintype "passive"))
    )
    (net (code "118") (name "unconnected-(DAD1P-Pad19)") (class "Default")
      (node (ref "DAD1P") (pin "19") (pinfunction "19_19") (pintype "passive"))
    )
    (net (code "119") (name "unconnected-(DAD2P-Pad19)") (class "Default")
      (node (ref "DAD2P") (pin "19") (pinfunction "19_19") (pintype "passive"))
    )
    (net (code "120") (name "unconnected-(DAT1P-Pad19)") (class "Default")
      (node (ref "DAT1P") (pin "19") (pinfunction "19_19") (pintype "passive"))
    )
    (net (code "121") (name "unconnected-(DAT2P-Pad19)") (class "Default")
      (node (ref "DAT2P") (pin "19") (pinfunction "19_19") (pintype "passive"))
    )
    (net (code "122") (name "unconnected-(MEM1P-Pad19)") (class "Default")
      (node (ref "MEM1P") (pin "19") (pinfunction "19_19") (pintype "passive"))
    )
    (net (code "123") (name "unconnected-(MEM2P-Pad5)") (class "Default")
      (node (ref "MEM2P") (pin "5") (pinfunction "5_5") (pintype "passive"))
    )
    (net (code "124") (name "unconnected-(MEM2P-Pad7)") (class "Default")
      (node (ref "MEM2P") (pin "7") (pinfunction "7_7") (pintype "passive"))
    )
    (net (code "125") (name "unconnected-(MEM2P-Pad19)") (class "Default")
      (node (ref "MEM2P") (pin "19") (pinfunction "19_19") (pintype "passive"))
    )
    (net (code "126") (name "unconnected-(MM32KQ-IN{slash}GCLK2{slash}OE2-Pad90)") (class "Default")
      (node (ref "MM32K") (pin "90") (pinfunction "IN/GCLK2/OE2_90") (pintype "input"))
    )
    (net (code "127") (name "unconnected-(MM32KQ-IN{slash}GCLR-Pad89)") (class "Default")
      (node (ref "MM32K") (pin "89") (pinfunction "IN/GCLR_89") (pintype "input"))
    )
    (net (code "128") (name "unconnected-(MM32KQ-IN{slash}OE1-Pad88)") (class "Default")
      (node (ref "MM32K") (pin "88") (pinfunction "IN/OE1_88") (pintype "input"))
    )
    (net (code "129") (name "unconnected-(MM32KQ-IO3-Pad5)") (class "Default")
      (node (ref "MM32K") (pin "5") (pinfunction "IO3_5") (pintype "bidirectional"))
    )
    (net (code "130") (name "unconnected-(MM32KQ-IO44-Pad55)") (class "Default")
      (node (ref "MM32K") (pin "55") (pinfunction "IO44_55") (pintype "bidirectional"))
    )
    (net (code "131") (name "unconnected-(MM32KQ-IO48-Pad60)") (class "Default")
      (node (ref "MM32K") (pin "60") (pinfunction "IO48_60") (pintype "bidirectional"))
    )
    (net (code "132") (name "unconnected-(MM32KQ-IO49-Pad61)") (class "Default")
      (node (ref "MM32K") (pin "61") (pinfunction "IO49_61") (pintype "bidirectional"))
    )
    (net (code "133") (name "unconnected-(MM32KQ-IO50-Pad63)") (class "Default")
      (node (ref "MM32K") (pin "63") (pinfunction "IO50_63") (pintype "bidirectional"))
    )
    (net (code "134") (name "unconnected-(MM32KQ-IO75-Pad99)") (class "Default")
      (node (ref "MM32K") (pin "99") (pinfunction "IO75_99") (pintype "bidirectional"))
    )
    (net (code "135") (name "unconnected-(MM32KQ-IO76-Pad100)") (class "Default")
      (node (ref "MM32K") (pin "100") (pinfunction "IO76_100") (pintype "bidirectional"))
    )
    (net (code "136") (name "unconnected-(MM32KQ-IO{slash}PD1-Pad1)") (class "Default")
      (node (ref "MM32K") (pin "1") (pinfunction "IO/PD1_1") (pintype "bidirectional"))
    )
    (net (code "137") (name "unconnected-(MMU8LQ-IN{slash}OE1-Pad88)") (class "Default")
      (node (ref "MMU8L") (pin "88") (pinfunction "IN/OE1_88") (pintype "input"))
    )
    (net (code "138") (name "unconnected-(MMU8LQ-IO28-Pad35)") (class "Default")
      (node (ref "MMU8L") (pin "35") (pinfunction "IO28_35") (pintype "bidirectional"))
    )
    (net (code "139") (name "unconnected-(MMU8LQ-IO41-Pad52)") (class "Default")
      (node (ref "MMU8L") (pin "52") (pinfunction "IO41_52") (pintype "bidirectional"))
    )
    (net (code "140") (name "unconnected-(MMU8LQ-IO69-Pad92)") (class "Default")
      (node (ref "MMU8L") (pin "92") (pinfunction "IO69_92") (pintype "bidirectional"))
    )
    (net (code "141") (name "unconnected-(MMU8LQ-IO72-Pad96)") (class "Default")
      (node (ref "MMU8L") (pin "96") (pinfunction "IO72_96") (pintype "bidirectional"))
    )
    (net (code "142") (name "unconnected-(MMU8LQ-IO75-Pad99)") (class "Default")
      (node (ref "MMU8L") (pin "99") (pinfunction "IO75_99") (pintype "bidirectional"))
    )
    (net (code "143") (name "unconnected-(MMU8LQ-IO76-Pad100)") (class "Default")
      (node (ref "MMU8L") (pin "100") (pinfunction "IO76_100") (pintype "bidirectional"))
    )
    (net (code "144") (name "unconnected-(PANEL-Pad19)") (class "Default")
      (node (ref "PANEL") (pin "19") (pinfunction "19_19") (pintype "passive"))
    )
    (net (code "145") (name "unconnected-(PROG1-Pad6)") (class "Default")
      (node (ref "PROG1") (pin "6") (pinfunction "6_6") (pintype "passive"))
    )
    (net (code "146") (name "unconnected-(PROG1-Pad7)") (class "Default")
      (node (ref "PROG1") (pin "7") (pinfunction "7_7") (pintype "passive"))
    )
    (net (code "147") (name "unconnected-(PROG1-Pad8)") (class "Default")
      (node (ref "PROG1") (pin "8") (pinfunction "8_8") (pintype "passive"))
    )
    (net (code "148") (name "unconnected-(PROG2-Pad6)") (class "Default")
      (node (ref "PROG2") (pin "6") (pinfunction "6_6") (pintype "passive"))
    )
    (net (code "149") (name "unconnected-(PROG2-Pad7)") (class "Default")
      (node (ref "PROG2") (pin "7") (pinfunction "7_7") (pintype "passive"))
    )
    (net (code "150") (name "unconnected-(PROG2-Pad8)") (class "Default")
      (node (ref "PROG2") (pin "8") (pinfunction "8_8") (pintype "passive"))
    )
    (net (code "151") (name "~{ACLR}") (class "Default")
      (node (ref "ACB2P") (pin "7") (pinfunction "7_7") (pintype "passive"))
      (node (ref "MMU8L") (pin "76") (pinfunction "IO60_76") (pintype "bidirectional"))
    )
    (net (code "152") (name "~{ADDA}") (class "Default")
      (node (ref "DAD2P") (pin "5") (pinfunction "5_5") (pintype "passive"))
    )
    (net (code "153") (name "~{BF_ENABLE}") (class "Default")
      (node (ref "CPU1P") (pin "13") (pinfunction "13_13") (pintype "passive"))
      (node (ref "MMU8L") (pin "14") (pinfunction "IO11_14") (pintype "bidirectional"))
    )
    (net (code "154") (name "~{BREAK}") (class "Default")
      (node (ref "DAD2P") (pin "7") (pinfunction "7_7") (pintype "passive"))
    )
    (net (code "155") (name "~{BRQ}") (class "Default")
      (node (ref "DAD2P") (pin "11") (pinfunction "11_11") (pintype "passive"))
    )
    (net (code "156") (name "~{CANCR}") (class "Default")
      (node (ref "DAT2P") (pin "9") (pinfunction "9_9") (pintype "passive"))
    )
    (net (code "157") (name "~{CS}") (class "Default")
      (node (ref "E3") (pin "20") (pinfunction "~{CS}_20") (pintype "input"))
      (node (ref "E3A") (pin "20") (pinfunction "~{CS}_20") (pintype "input"))
      (node (ref "E4") (pin "20") (pinfunction "~{CS}_20") (pintype "input"))
      (node (ref "E4A") (pin "20") (pinfunction "~{CS}_20") (pintype "input"))
      (node (ref "MM32K") (pin "50") (pinfunction "IO40_50") (pintype "bidirectional"))
    )
    (net (code "158") (name "~{CYC3}") (class "Default")
      (node (ref "DAT2P") (pin "11") (pinfunction "11_11") (pintype "passive"))
    )
    (net (code "159") (name "~{D-IN}") (class "Default")
      (node (ref "DAD2P") (pin "9") (pinfunction "9_9") (pintype "passive"))
    )
    (net (code "160") (name "~{DAD00}") (class "Default")
      (node (ref "DAD1P") (pin "17") (pinfunction "17_17") (pintype "passive"))
    )
    (net (code "161") (name "~{DAD01}") (class "Default")
      (node (ref "DAD1P") (pin "15") (pinfunction "15_15") (pintype "passive"))
    )
    (net (code "162") (name "~{DAD02}") (class "Default")
      (node (ref "DAD1P") (pin "13") (pinfunction "13_13") (pintype "passive"))
    )
    (net (code "163") (name "~{DAD03}") (class "Default")
      (node (ref "DAD1P") (pin "11") (pinfunction "11_11") (pintype "passive"))
    )
    (net (code "164") (name "~{DAD04}") (class "Default")
      (node (ref "DAD1P") (pin "9") (pinfunction "9_9") (pintype "passive"))
    )
    (net (code "165") (name "~{DAD05}") (class "Default")
      (node (ref "DAD1P") (pin "7") (pinfunction "7_7") (pintype "passive"))
    )
    (net (code "166") (name "~{DAD06}") (class "Default")
      (node (ref "DAD1P") (pin "5") (pinfunction "5_5") (pintype "passive"))
    )
    (net (code "167") (name "~{DAD07}") (class "Default")
      (node (ref "DAD1P") (pin "3") (pinfunction "3_3") (pintype "passive"))
    )
    (net (code "168") (name "~{DAD08}") (class "Default")
      (node (ref "DAD1P") (pin "1") (pinfunction "1_1") (pintype "passive"))
    )
    (net (code "169") (name "~{DAD09}") (class "Default")
      (node (ref "DAD2P") (pin "17") (pinfunction "17_17") (pintype "passive"))
    )
    (net (code "170") (name "~{DAD10}") (class "Default")
      (node (ref "DAD2P") (pin "15") (pinfunction "15_15") (pintype "passive"))
    )
    (net (code "171") (name "~{DAD11}") (class "Default")
      (node (ref "DAD2P") (pin "13") (pinfunction "13_13") (pintype "passive"))
    )
    (net (code "172") (name "~{DAT00}") (class "Default")
      (node (ref "DAT1P") (pin "17") (pinfunction "17_17") (pintype "passive"))
    )
    (net (code "173") (name "~{DAT01}") (class "Default")
      (node (ref "DAT1P") (pin "15") (pinfunction "15_15") (pintype "passive"))
    )
    (net (code "174") (name "~{DAT02}") (class "Default")
      (node (ref "DAT1P") (pin "13") (pinfunction "13_13") (pintype "passive"))
    )
    (net (code "175") (name "~{DAT03}") (class "Default")
      (node (ref "DAT1P") (pin "11") (pinfunction "11_11") (pintype "passive"))
    )
    (net (code "176") (name "~{DAT04}") (class "Default")
      (node (ref "DAT1P") (pin "9") (pinfunction "9_9") (pintype "passive"))
    )
    (net (code "177") (name "~{DAT05}") (class "Default")
      (node (ref "DAT1P") (pin "7") (pinfunction "7_7") (pintype "passive"))
    )
    (net (code "178") (name "~{DAT06}") (class "Default")
      (node (ref "DAT1P") (pin "5") (pinfunction "5_5") (pintype "passive"))
    )
    (net (code "179") (name "~{DAT07}") (class "Default")
      (node (ref "DAT1P") (pin "3") (pinfunction "3_3") (pintype "passive"))
    )
    (net (code "180") (name "~{DAT08}") (class "Default")
      (node (ref "DAT1P") (pin "1") (pinfunction "1_1") (pintype "passive"))
    )
    (net (code "181") (name "~{DAT09}") (class "Default")
      (node (ref "DAT2P") (pin "17") (pinfunction "17_17") (pintype "passive"))
    )
    (net (code "182") (name "~{DAT10}") (class "Default")
      (node (ref "DAT2P") (pin "15") (pinfunction "15_15") (pintype "passive"))
    )
    (net (code "183") (name "~{DAT11}") (class "Default")
      (node (ref "DAT2P") (pin "13") (pinfunction "13_13") (pintype "passive"))
    )
    (net (code "184") (name "~{DF_ENABLE}") (class "Default")
      (node (ref "CPU1P") (pin "17") (pinfunction "17_17") (pintype "passive"))
      (node (ref "MMU8L") (pin "20") (pinfunction "IO15_20") (pintype "bidirectional"))
    )
    (net (code "185") (name "~{EA0}") (class "Default")
      (node (ref "MM32K") (pin "56") (pinfunction "IO45_56") (pintype "bidirectional"))
      (node (ref "PANEL") (pin "5") (pinfunction "5_5") (pintype "passive"))
    )
    (net (code "186") (name "~{EA1}") (class "Default")
      (node (ref "MM32K") (pin "57") (pinfunction "IO46_57") (pintype "bidirectional"))
      (node (ref "PANEL") (pin "3") (pinfunction "3_3") (pintype "passive"))
    )
    (net (code "187") (name "~{EA2}") (class "Default")
      (node (ref "MM32K") (pin "58") (pinfunction "IO47_58") (pintype "bidirectional"))
      (node (ref "PANEL") (pin "1") (pinfunction "1_1") (pintype "passive"))
    )
    (net (code "188") (name "~{EA}") (class "Default")
      (node (ref "BMA1P") (pin "17") (pinfunction "17_17") (pintype "passive"))
      (node (ref "MMU8L") (pin "24") (pinfunction "IO19_24") (pintype "bidirectional"))
    )
    (net (code "189") (name "~{EMA}") (class "Default")
      (node (ref "MEM2P") (pin "1") (pinfunction "1_1") (pintype "passive"))
      (node (ref "MM32K") (pin "93") (pinfunction "IO70_93") (pintype "bidirectional"))
      (node (ref "MMU8L") (pin "36") (pinfunction "IO29_36") (pintype "bidirectional"))
    )
    (net (code "190") (name "~{EXDA0}") (class "Default")
      (node (ref "DAT2P") (pin "1") (pinfunction "1_1") (pintype "passive"))
      (node (ref "MMU8L") (pin "21") (pinfunction "IO16_21") (pintype "bidirectional"))
    )
    (net (code "191") (name "~{EXDA1}") (class "Default")
      (node (ref "DAT2P") (pin "3") (pinfunction "3_3") (pintype "passive"))
      (node (ref "MMU8L") (pin "22") (pinfunction "IO17_22") (pintype "bidirectional"))
    )
    (net (code "192") (name "~{EXDA2}") (class "Default")
      (node (ref "DAT2P") (pin "5") (pinfunction "5_5") (pintype "passive"))
      (node (ref "MMU8L") (pin "23") (pinfunction "IO18_23") (pintype "bidirectional"))
    )
    (net (code "193") (name "~{FS0}") (class "Default")
      (node (ref "FIELDS") (pin "16") (pinfunction "16_16") (pintype "passive"))
      (node (ref "MM32K") (pin "30") (pinfunction "IO24_30") (pintype "bidirectional"))
    )
    (net (code "194") (name "~{FS1}") (class "Default")
      (node (ref "FIELDS") (pin "14") (pinfunction "14_14") (pintype "passive"))
      (node (ref "MM32K") (pin "29") (pinfunction "IO23_29") (pintype "bidirectional"))
    )
    (net (code "195") (name "~{FS2}") (class "Default")
      (node (ref "FIELDS") (pin "12") (pinfunction "12_12") (pintype "passive"))
      (node (ref "MM32K") (pin "28") (pinfunction "IO22_28") (pintype "bidirectional"))
    )
    (net (code "196") (name "~{FS3}") (class "Default")
      (node (ref "FIELDS") (pin "10") (pinfunction "10_10") (pintype "passive"))
      (node (ref "MM32K") (pin "27") (pinfunction "IO21_27") (pintype "bidirectional"))
    )
    (net (code "197") (name "~{FS4}") (class "Default")
      (node (ref "FIELDS") (pin "8") (pinfunction "8_8") (pintype "passive"))
      (node (ref "MM32K") (pin "25") (pinfunction "IO20_25") (pintype "bidirectional"))
    )
    (net (code "198") (name "~{FS5}") (class "Default")
      (node (ref "FIELDS") (pin "6") (pinfunction "6_6") (pintype "passive"))
      (node (ref "MM32K") (pin "24") (pinfunction "IO19_24") (pintype "bidirectional"))
    )
    (net (code "199") (name "~{FS6}") (class "Default")
      (node (ref "FIELDS") (pin "4") (pinfunction "4_4") (pintype "passive"))
      (node (ref "MM32K") (pin "23") (pinfunction "IO18_23") (pintype "bidirectional"))
    )
    (net (code "200") (name "~{FS7}") (class "Default")
      (node (ref "FIELDS") (pin "2") (pinfunction "2_2") (pintype "passive"))
      (node (ref "MM32K") (pin "22") (pinfunction "IO17_22") (pintype "bidirectional"))
    )
    (net (code "201") (name "~{IB00}") (class "Default")
      (node (ref "ACB1P") (pin "17") (pinfunction "17_17") (pintype "passive"))
      (node (ref "MMU8L") (pin "64") (pinfunction "IO51_64") (pintype "bidirectional"))
    )
    (net (code "202") (name "~{IB01}") (class "Default")
      (node (ref "ACB1P") (pin "15") (pinfunction "15_15") (pintype "passive"))
      (node (ref "MMU8L") (pin "67") (pinfunction "IO53_67") (pintype "bidirectional"))
    )
    (net (code "203") (name "~{IB02}") (class "Default")
      (node (ref "ACB1P") (pin "13") (pinfunction "13_13") (pintype "passive"))
      (node (ref "MMU8L") (pin "69") (pinfunction "IO55_69") (pintype "bidirectional"))
    )
    (net (code "204") (name "~{IB03}") (class "Default")
      (node (ref "ACB1P") (pin "11") (pinfunction "11_11") (pintype "passive"))
      (node (ref "MMU8L") (pin "71") (pinfunction "IO57_71") (pintype "bidirectional"))
    )
    (net (code "205") (name "~{IB04}") (class "Default")
      (node (ref "ACB1P") (pin "9") (pinfunction "9_9") (pintype "passive"))
      (node (ref "MMU8L") (pin "75") (pinfunction "IO59_75") (pintype "bidirectional"))
    )
    (net (code "206") (name "~{IB05}") (class "Default")
      (node (ref "ACB1P") (pin "7") (pinfunction "7_7") (pintype "passive"))
      (node (ref "MMU8L") (pin "77") (pinfunction "IO61_77") (pintype "bidirectional"))
    )
    (net (code "207") (name "~{IB06}") (class "Default")
      (node (ref "ACB1P") (pin "5") (pinfunction "5_5") (pintype "passive"))
      (node (ref "MMU8L") (pin "79") (pinfunction "IO63_79") (pintype "bidirectional"))
    )
    (net (code "208") (name "~{IB07}") (class "Default")
      (node (ref "ACB1P") (pin "3") (pinfunction "3_3") (pintype "passive"))
      (node (ref "MMU8L") (pin "81") (pinfunction "IO65_81") (pintype "bidirectional"))
    )
    (net (code "209") (name "~{IB08}") (class "Default")
      (node (ref "ACB1P") (pin "1") (pinfunction "1_1") (pintype "passive"))
      (node (ref "MMU8L") (pin "84") (pinfunction "IO67_84") (pintype "bidirectional"))
    )
    (net (code "210") (name "~{IB09}") (class "Default")
      (node (ref "ACB2P") (pin "17") (pinfunction "17_17") (pintype "passive"))
      (node (ref "MMU8L") (pin "63") (pinfunction "IO50_63") (pintype "bidirectional"))
    )
    (net (code "211") (name "~{IB10}") (class "Default")
      (node (ref "ACB2P") (pin "15") (pinfunction "15_15") (pintype "passive"))
      (node (ref "MMU8L") (pin "65") (pinfunction "IO52_65") (pintype "bidirectional"))
    )
    (net (code "212") (name "~{IB11}") (class "Default")
      (node (ref "ACB2P") (pin "13") (pinfunction "13_13") (pintype "passive"))
      (node (ref "MMU8L") (pin "68") (pinfunction "IO54_68") (pintype "bidirectional"))
    )
    (net (code "213") (name "~{INT_INH}") (class "Default")
      (node (ref "CPU1P") (pin "7") (pinfunction "7_7") (pintype "passive"))
      (node (ref "MMU8L") (pin "9") (pinfunction "IO7_9") (pintype "bidirectional"))
    )
    (net (code "214") (name "~{IRQ}") (class "Default")
      (node (ref "ACB2P") (pin "9") (pinfunction "9_9") (pintype "passive"))
      (node (ref "MMU8L") (pin "72") (pinfunction "IO58_72") (pintype "bidirectional"))
    )
    (net (code "215") (name "~{KEY_CLR}") (class "Default")
      (node (ref "CPU1P") (pin "9") (pinfunction "9_9") (pintype "passive"))
      (node (ref "MMU8L") (pin "10") (pinfunction "IO8_10") (pintype "bidirectional"))
    )
    (net (code "216") (name "~{KEY_DF0}") (class "Default")
      (node (ref "MMU8L") (pin "98") (pinfunction "IO74_98") (pintype "bidirectional"))
      (node (ref "PANEL") (pin "11") (pinfunction "11_11") (pintype "passive"))
    )
    (net (code "217") (name "~{KEY_DF1}") (class "Default")
      (node (ref "MMU8L") (pin "97") (pinfunction "IO73_97") (pintype "bidirectional"))
      (node (ref "PANEL") (pin "9") (pinfunction "9_9") (pintype "passive"))
    )
    (net (code "218") (name "~{KEY_DF2}") (class "Default")
      (node (ref "CPU1P") (pin "1") (pinfunction "1_1") (pintype "passive"))
      (node (ref "MMU8L") (pin "2") (pinfunction "IO2_2") (pintype "bidirectional"))
      (node (ref "PANEL") (pin "7") (pinfunction "7_7") (pintype "passive"))
    )
    (net (code "219") (name "~{KEY_IF0}") (class "Default")
      (node (ref "MMU8L") (pin "93") (pinfunction "IO70_93") (pintype "bidirectional"))
      (node (ref "PANEL") (pin "17") (pinfunction "17_17") (pintype "passive"))
    )
    (net (code "220") (name "~{KEY_IF1}") (class "Default")
      (node (ref "MMU8L") (pin "94") (pinfunction "IO71_94") (pintype "bidirectional"))
      (node (ref "PANEL") (pin "15") (pinfunction "15_15") (pintype "passive"))
    )
    (net (code "221") (name "~{KEY_IF2}") (class "Default")
      (node (ref "CPU1P") (pin "3") (pinfunction "3_3") (pintype "passive"))
      (node (ref "MMU8L") (pin "6") (pinfunction "IO4_6") (pintype "bidirectional"))
      (node (ref "PANEL") (pin "13") (pinfunction "13_13") (pintype "passive"))
    )
    (net (code "222") (name "~{KEY_LOAD}") (class "Default")
      (node (ref "CPU2P") (pin "13") (pinfunction "13_13") (pintype "passive"))
      (node (ref "MMU8L") (pin "13") (pinfunction "IO10_13") (pintype "bidirectional"))
    )
    (net (code "223") (name "~{LINE}") (class "Default")
      (node (ref "ACB2P") (pin "1") (pinfunction "1_1") (pintype "passive"))
      (node (ref "MMU8L") (pin "83") (pinfunction "IO66_83") (pintype "bidirectional"))
    )
    (net (code "224") (name "~{LOAD_SF}") (class "Default")
      (node (ref "CPU1P") (pin "5") (pinfunction "5_5") (pintype "passive"))
      (node (ref "MMU8L") (pin "8") (pinfunction "IO6_8") (pintype "bidirectional"))
    )
    (net (code "225") (name "~{MB03}") (class "Default")
      (node (ref "BMB1P") (pin "11") (pinfunction "11_11") (pintype "passive"))
    )
    (net (code "226") (name "~{MB04}") (class "Default")
      (node (ref "BMB1P") (pin "7") (pinfunction "7_7") (pintype "passive"))
    )
    (net (code "227") (name "~{MB05}") (class "Default")
      (node (ref "BMB1P") (pin "3") (pinfunction "3_3") (pintype "passive"))
    )
    (net (code "228") (name "~{MB06}") (class "Default")
      (node (ref "BMB2P") (pin "17") (pinfunction "17_17") (pintype "passive"))
    )
    (net (code "229") (name "~{MB07}") (class "Default")
      (node (ref "BMB2P") (pin "13") (pinfunction "13_13") (pintype "passive"))
    )
    (net (code "230") (name "~{MB08}") (class "Default")
      (node (ref "BMB2P") (pin "9") (pinfunction "9_9") (pintype "passive"))
    )
    (net (code "231") (name "~{MEMDONE}") (class "Default")
      (node (ref "BMA2P") (pin "1") (pinfunction "1_1") (pintype "passive"))
      (node (ref "MM32K") (pin "98") (pinfunction "IO74_98") (pintype "bidirectional"))
      (node (ref "MMU8L") (pin "29") (pinfunction "IO23_29") (pintype "bidirectional"))
    )
    (net (code "232") (name "~{MNCR}") (class "Default")
      (node (ref "DAD2P") (pin "3") (pinfunction "3_3") (pintype "passive"))
    )
    (net (code "233") (name "~{OE}") (class "Default")
      (node (ref "E3") (pin "22") (pinfunction "~{OE}_22") (pintype "input"))
      (node (ref "E3A") (pin "22") (pinfunction "~{OE}_22") (pintype "input"))
      (node (ref "E4") (pin "22") (pinfunction "~{OE}_22") (pintype "input"))
      (node (ref "E4A") (pin "22") (pinfunction "~{OE}_22") (pintype "input"))
      (node (ref "MM32K") (pin "49") (pinfunction "IO39_49") (pintype "bidirectional"))
    )
    (net (code "234") (name "~{RUN}") (class "Default")
      (node (ref "ACB2P") (pin "5") (pinfunction "5_5") (pintype "passive"))
      (node (ref "MMU8L") (pin "78") (pinfunction "IO62_78") (pintype "bidirectional"))
    )
    (net (code "235") (name "~{SKIP}") (class "Default")
      (node (ref "ACB2P") (pin "11") (pinfunction "11_11") (pintype "passive"))
      (node (ref "MMU8L") (pin "70") (pinfunction "IO56_70") (pintype "bidirectional"))
    )
    (net (code "236") (name "~{SP_CYC_NEXT}") (class "Default")
      (node (ref "CPU1P") (pin "15") (pinfunction "15_15") (pintype "passive"))
      (node (ref "MMU8L") (pin "17") (pinfunction "IO13_17") (pintype "bidirectional"))
    )
    (net (code "237") (name "~{STROBE}") (class "Default")
      (node (ref "BMA2P") (pin "5") (pinfunction "5_5") (pintype "passive"))
      (node (ref "MM32K") (pin "96") (pinfunction "IO72_96") (pintype "bidirectional"))
      (node (ref "MMU8L") (pin "31") (pinfunction "IO25_31") (pintype "bidirectional"))
    )
    (net (code "238") (name "~{TTINST}") (class "Default")
      (node (ref "ACB2P") (pin "3") (pinfunction "3_3") (pintype "passive"))
      (node (ref "MMU8L") (pin "80") (pinfunction "IO64_80") (pintype "bidirectional"))
    )
    (net (code "239") (name "~{WCOVF}") (class "Default")
      (node (ref "DAT2P") (pin "7") (pinfunction "7_7") (pintype "passive"))
    )
    (net (code "240") (name "~{WE}") (class "Default")
      (node (ref "E3") (pin "27") (pinfunction "~{WE}_27") (pintype "input"))
      (node (ref "E3A") (pin "27") (pinfunction "~{WE}_27") (pintype "input"))
      (node (ref "E4") (pin "27") (pinfunction "~{WE}_27") (pintype "input"))
      (node (ref "E4A") (pin "27") (pinfunction "~{WE}_27") (pintype "input"))
      (node (ref "MM32K") (pin "48") (pinfunction "IO38_48") (pintype "bidirectional"))
    )
  )
)
